# yacc1.net
KiCad netlist of a schematic drawn in EAGLE
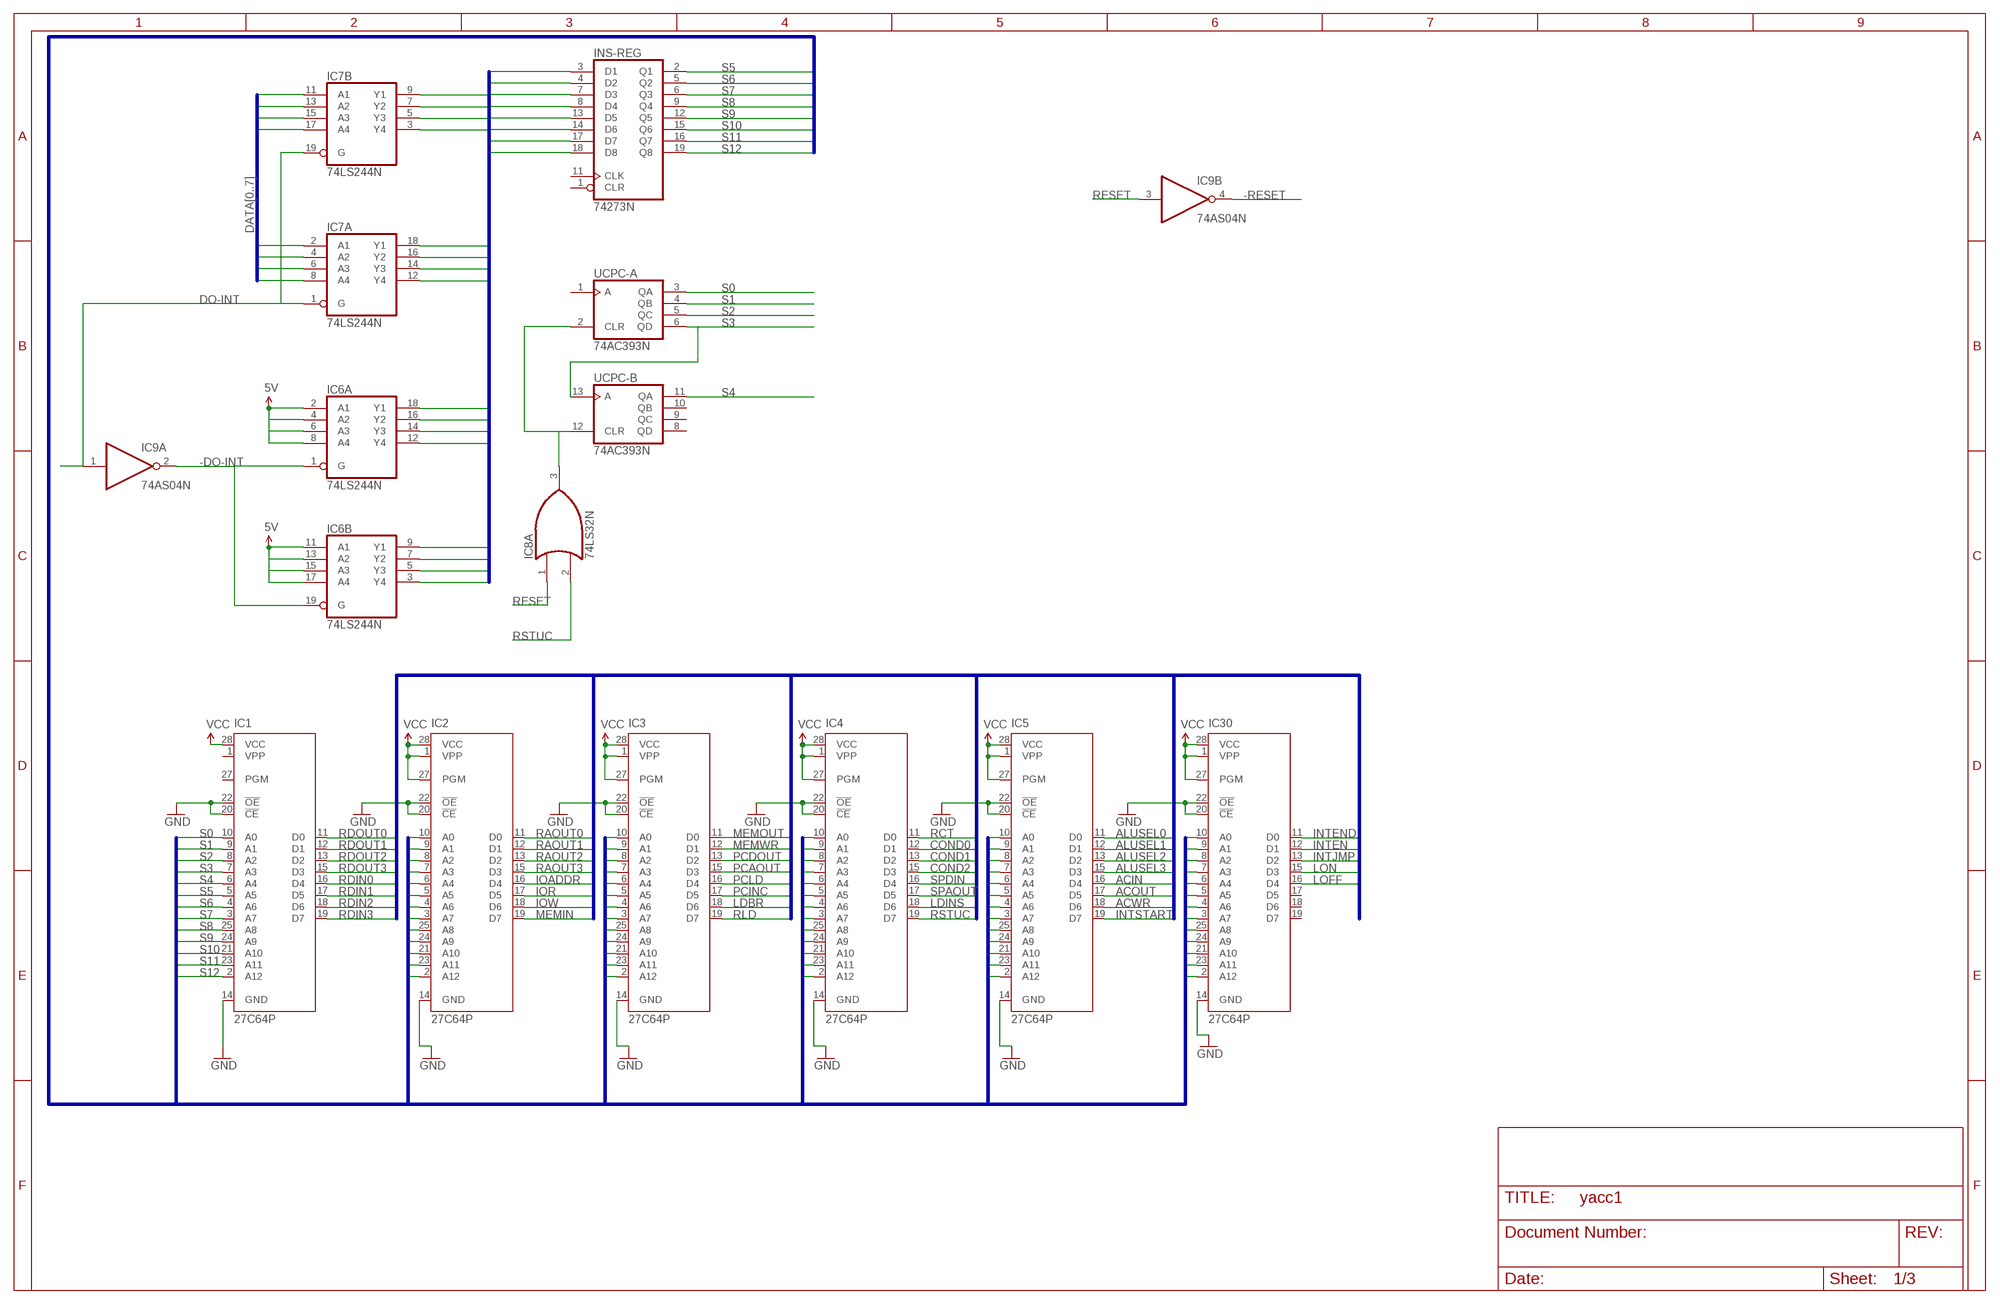
[diagram p0: schematic, sheet 1]
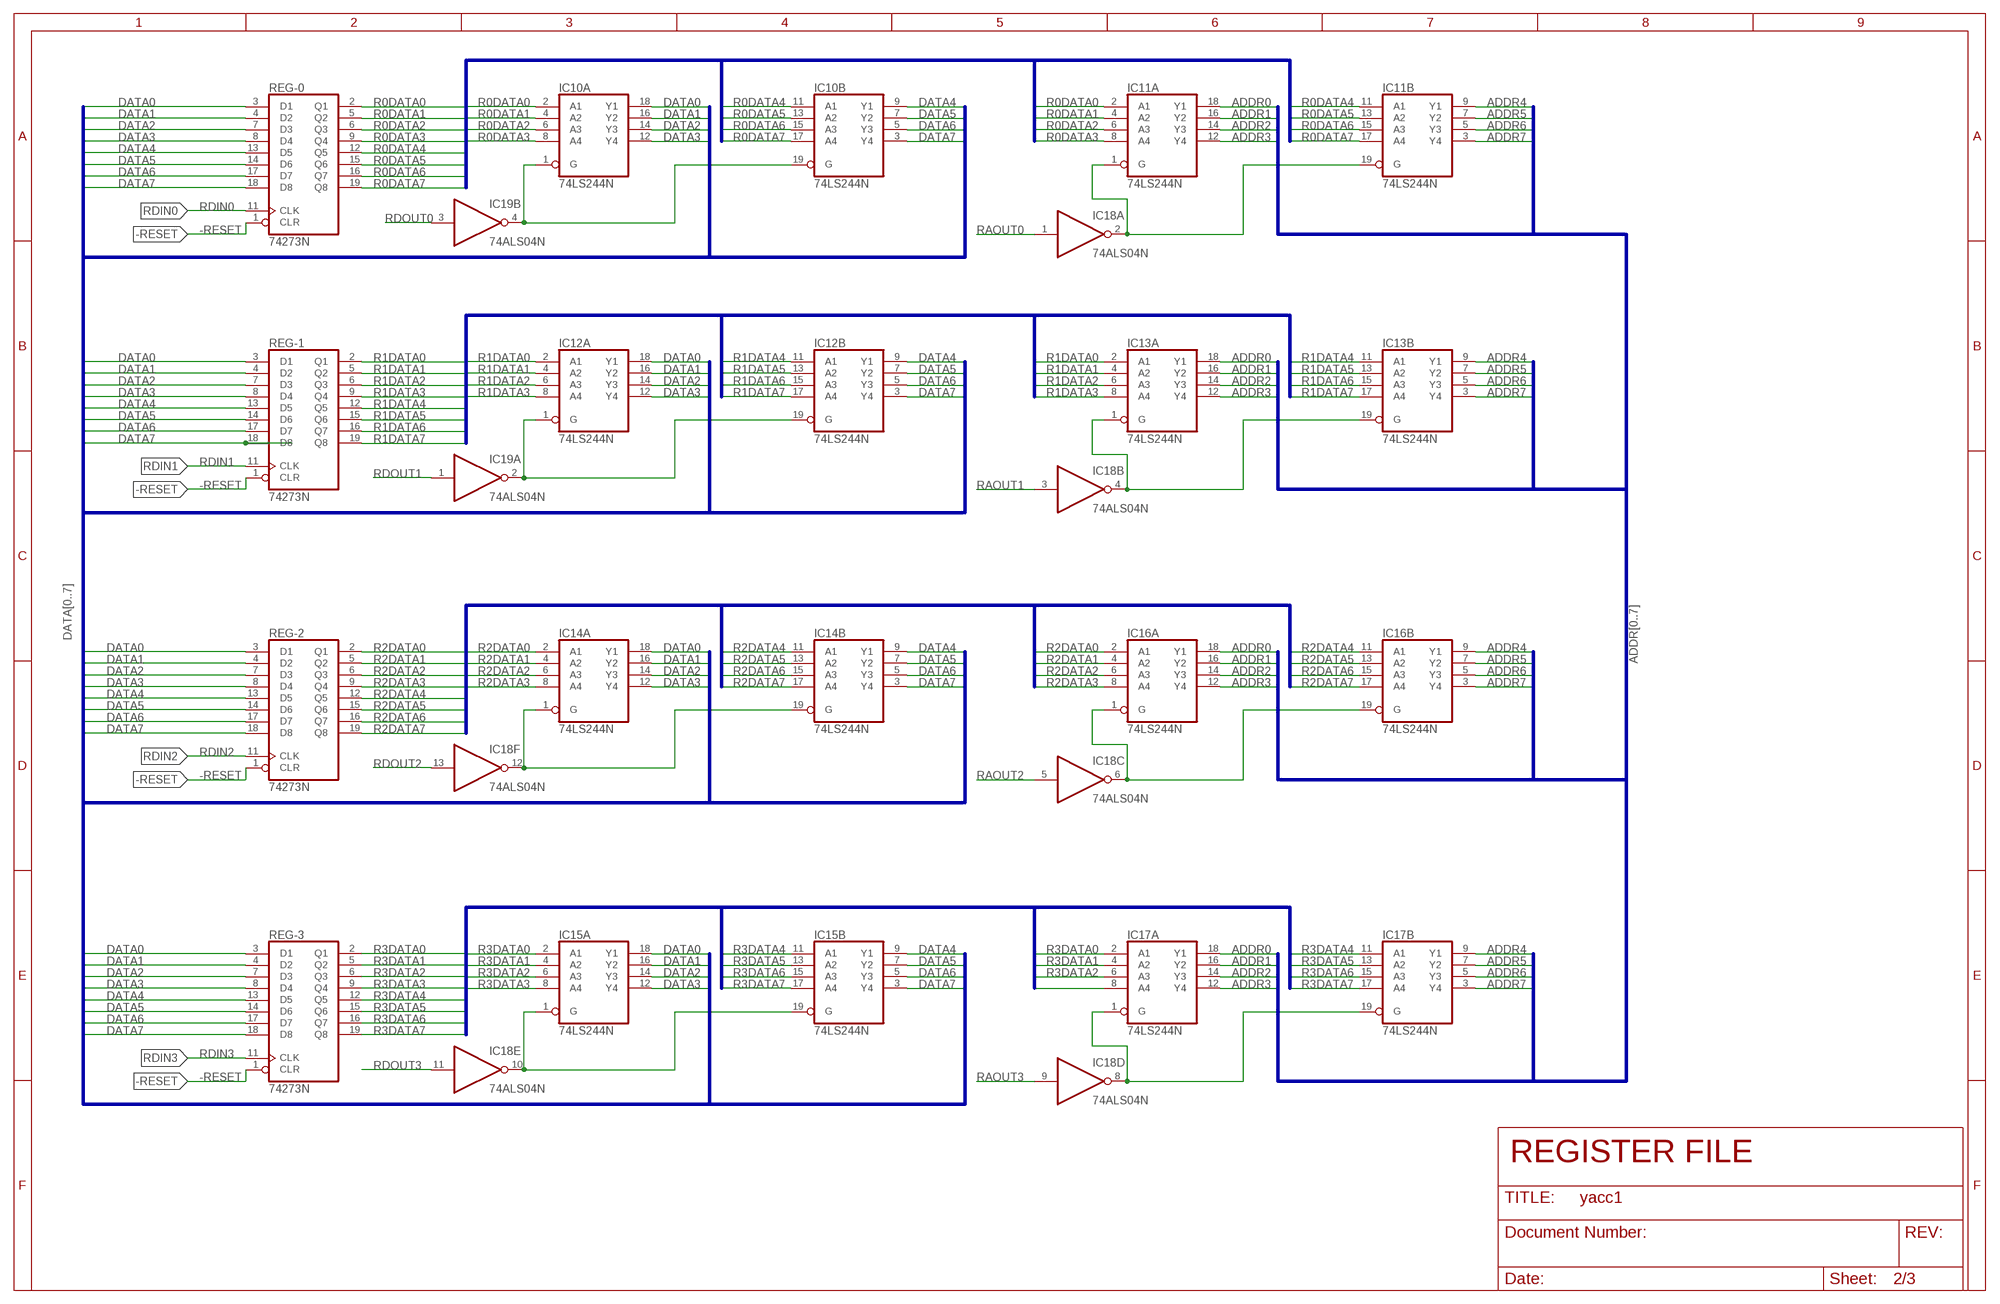
[diagram p1: schematic, sheet 2]
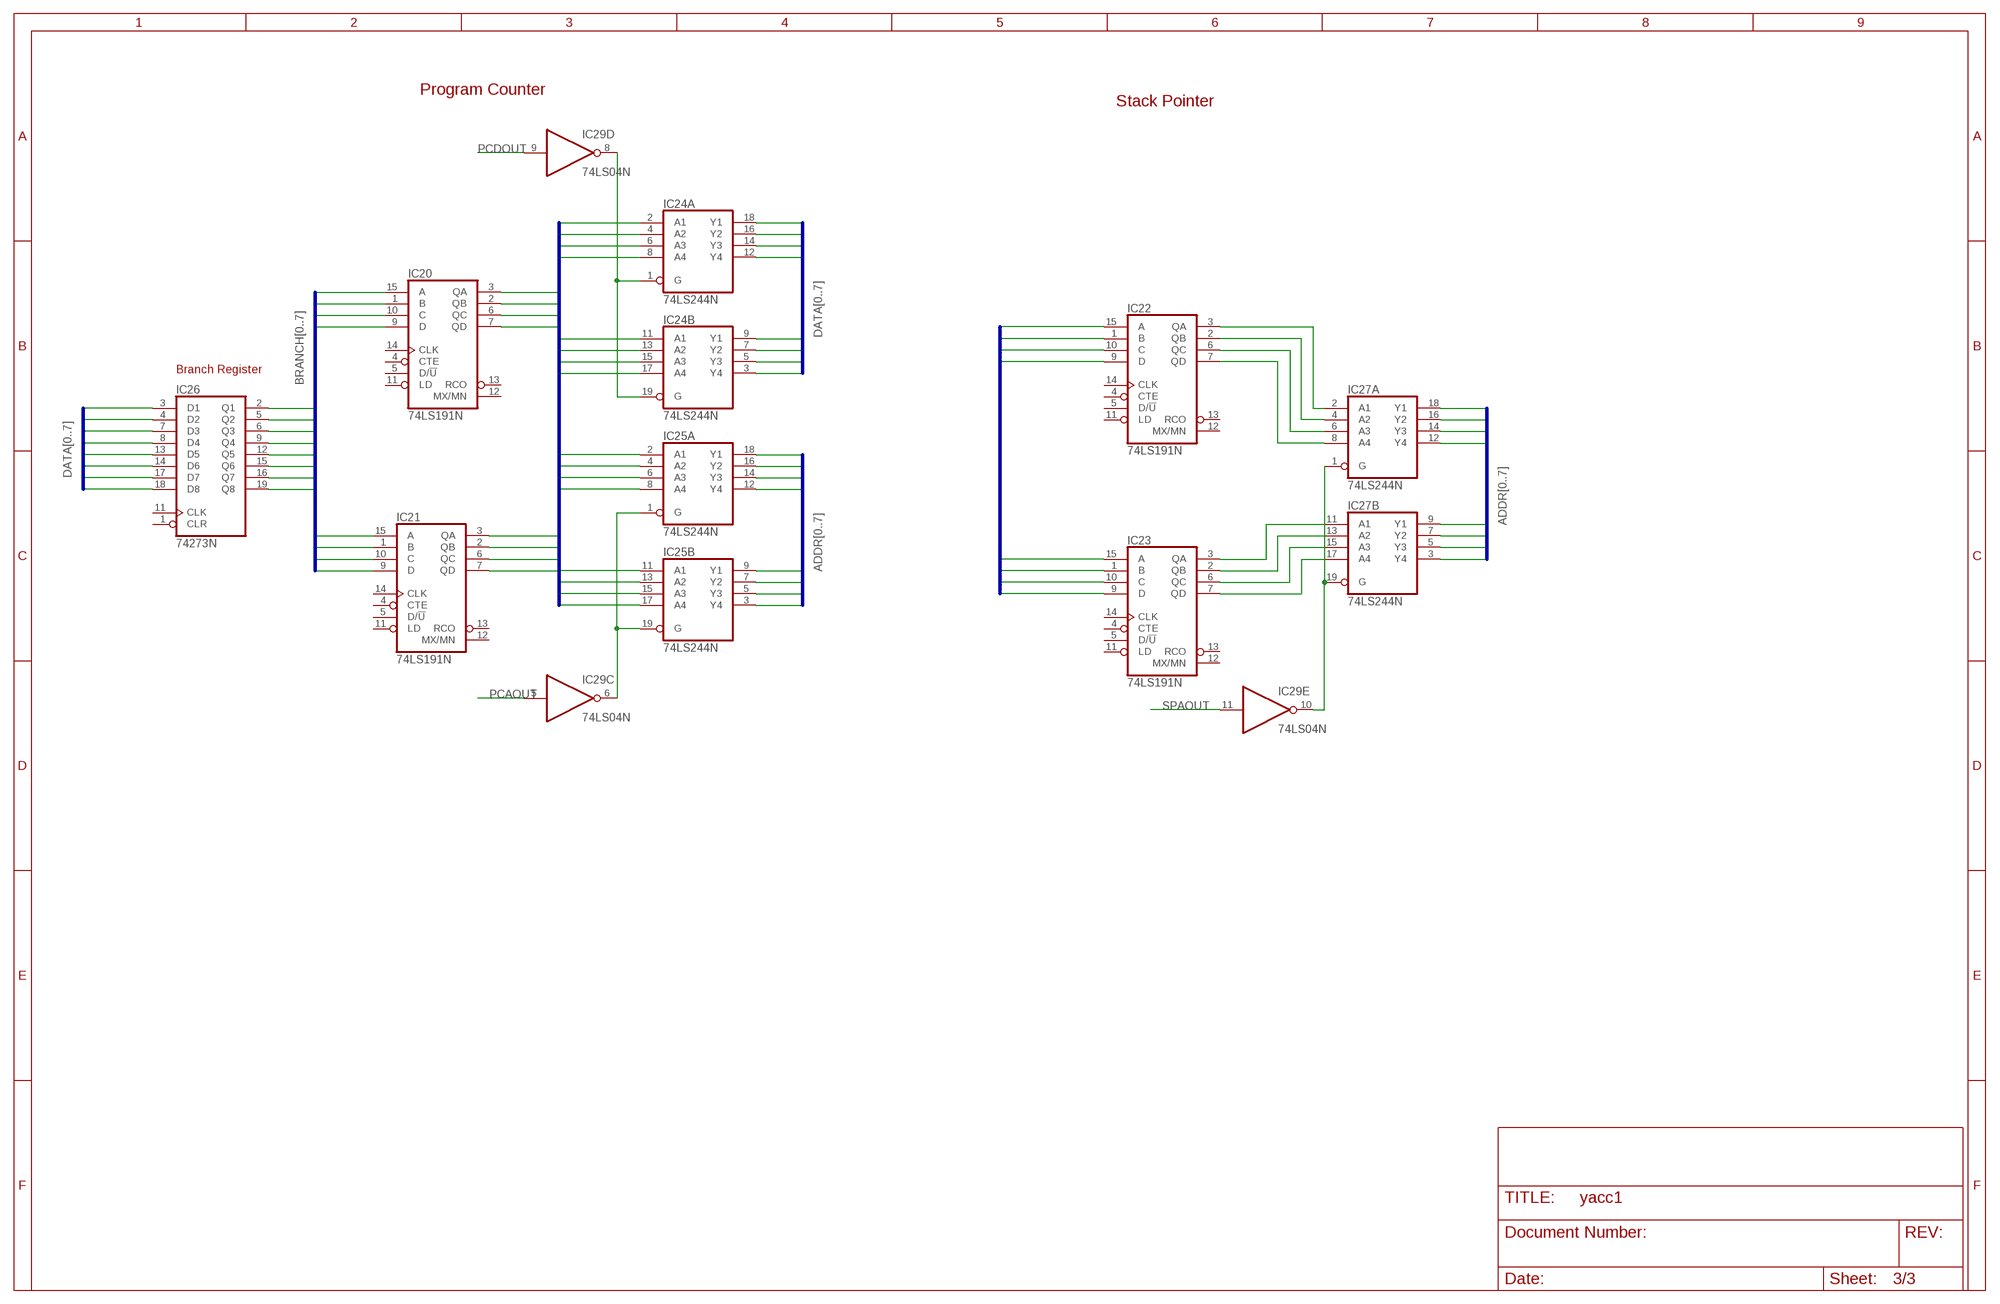
[diagram p2: schematic, sheet 3]

(export (version "E")
  (design (tool "Eeschema 10.0.6"))
  (components
    (comp (ref "IC20")
      (value "74LS191N")
      (footprint "eagle-import:DIL16")
      (libsource (lib "eagle-import") (part "74191NLS"))
    )
    (comp (ref "IC21")
      (value "74LS191N")
      (footprint "eagle-import:DIL16")
      (libsource (lib "eagle-import") (part "74191NLS"))
    )
    (comp (ref "IC22")
      (value "74LS191N")
      (footprint "eagle-import:DIL16")
      (libsource (lib "eagle-import") (part "74191NLS"))
    )
    (comp (ref "IC23")
      (value "74LS191N")
      (footprint "eagle-import:DIL16")
      (libsource (lib "eagle-import") (part "74191NLS"))
    )
    (comp (ref "IC24")
      (value "74LS244N")
      (footprint "eagle-import:DIL20")
      (libsource (lib "eagle-import") (part "74244NLS"))
    )
    (comp (ref "IC25")
      (value "74LS244N")
      (footprint "eagle-import:DIL20")
      (libsource (lib "eagle-import") (part "74244NLS"))
    )
    (comp (ref "IC26")
      (value "74273N")
      (footprint "eagle-import:DIL20")
      (libsource (lib "eagle-import") (part "74273N"))
    )
    (comp (ref "IC27")
      (value "74LS244N")
      (footprint "eagle-import:DIL20")
      (libsource (lib "eagle-import") (part "74244NLS"))
    )
    (comp (ref "IC29")
      (value "74LS04N")
      (footprint "eagle-import:DIL14")
      (libsource (lib "eagle-import") (part "7404NLS"))
    )
    (comp (ref "IC10")
      (value "74LS244N")
      (footprint "eagle-import:DIL20")
      (libsource (lib "eagle-import") (part "74244NLS"))
    )
    (comp (ref "IC11")
      (value "74LS244N")
      (footprint "eagle-import:DIL20")
      (libsource (lib "eagle-import") (part "74244NLS"))
    )
    (comp (ref "IC12")
      (value "74LS244N")
      (footprint "eagle-import:DIL20")
      (libsource (lib "eagle-import") (part "74244NLS"))
    )
    (comp (ref "IC13")
      (value "74LS244N")
      (footprint "eagle-import:DIL20")
      (libsource (lib "eagle-import") (part "74244NLS"))
    )
    (comp (ref "IC14")
      (value "74LS244N")
      (footprint "eagle-import:DIL20")
      (libsource (lib "eagle-import") (part "74244NLS"))
    )
    (comp (ref "IC15")
      (value "74LS244N")
      (footprint "eagle-import:DIL20")
      (libsource (lib "eagle-import") (part "74244NLS"))
    )
    (comp (ref "IC16")
      (value "74LS244N")
      (footprint "eagle-import:DIL20")
      (libsource (lib "eagle-import") (part "74244NLS"))
    )
    (comp (ref "IC17")
      (value "74LS244N")
      (footprint "eagle-import:DIL20")
      (libsource (lib "eagle-import") (part "74244NLS"))
    )
    (comp (ref "IC18")
      (value "74ALS04N")
      (footprint "eagle-import:DIL14")
      (libsource (lib "eagle-import") (part "7404NALS"))
    )
    (comp (ref "IC19")
      (value "74ALS04N")
      (footprint "eagle-import:DIL14")
      (libsource (lib "eagle-import") (part "7404NALS"))
    )
    (comp (ref "REG-0")
      (value "74273N")
      (footprint "eagle-import:DIL20")
      (libsource (lib "eagle-import") (part "74273N"))
    )
    (comp (ref "REG-1")
      (value "74273N")
      (footprint "eagle-import:DIL20")
      (libsource (lib "eagle-import") (part "74273N"))
    )
    (comp (ref "REG-2")
      (value "74273N")
      (footprint "eagle-import:DIL20")
      (libsource (lib "eagle-import") (part "74273N"))
    )
    (comp (ref "REG-3")
      (value "74273N")
      (footprint "eagle-import:DIL20")
      (libsource (lib "eagle-import") (part "74273N"))
    )
    (comp (ref "IC1")
      (value "27C64P")
      (footprint "eagle-import:DIL28-6")
      (fields (field (name "MF") "Arrow Electronics") (field (name "MPN") "M27C64A-10F1"))
      (libsource (lib "eagle-import") (part "2764PC"))
    )
    (comp (ref "IC2")
      (value "27C64P")
      (footprint "eagle-import:DIL28-6")
      (fields (field (name "MF") "Arrow Electronics") (field (name "MPN") "M27C64A-10F1"))
      (libsource (lib "eagle-import") (part "2764PC"))
    )
    (comp (ref "IC3")
      (value "27C64P")
      (footprint "eagle-import:DIL28-6")
      (fields (field (name "MF") "Arrow Electronics") (field (name "MPN") "M27C64A-10F1"))
      (libsource (lib "eagle-import") (part "2764PC"))
    )
    (comp (ref "IC4")
      (value "27C64P")
      (footprint "eagle-import:DIL28-6")
      (fields (field (name "MF") "Arrow Electronics") (field (name "MPN") "M27C64A-10F1"))
      (libsource (lib "eagle-import") (part "2764PC"))
    )
    (comp (ref "IC5")
      (value "27C64P")
      (footprint "eagle-import:DIL28-6")
      (fields (field (name "MF") "Arrow Electronics") (field (name "MPN") "M27C64A-10F1"))
      (libsource (lib "eagle-import") (part "2764PC"))
    )
    (comp (ref "IC6")
      (value "74LS244N")
      (footprint "eagle-import:DIL20")
      (libsource (lib "eagle-import") (part "74244NLS"))
    )
    (comp (ref "IC7")
      (value "74LS244N")
      (footprint "eagle-import:DIL20")
      (libsource (lib "eagle-import") (part "74244NLS"))
    )
    (comp (ref "IC8")
      (value "74LS32N")
      (footprint "eagle-import:DIL14")
      (libsource (lib "eagle-import") (part "7432NLS"))
    )
    (comp (ref "IC9")
      (value "74AS04N")
      (footprint "eagle-import:DIL14")
      (libsource (lib "eagle-import") (part "7404NAS"))
    )
    (comp (ref "IC30")
      (value "27C64P")
      (footprint "eagle-import:DIL28-6")
      (fields (field (name "MF") "Arrow Electronics") (field (name "MPN") "M27C64A-10F1"))
      (libsource (lib "eagle-import") (part "2764PC"))
    )
    (comp (ref "INS-REG")
      (value "74273N")
      (footprint "eagle-import:DIL20")
      (libsource (lib "eagle-import") (part "74273N"))
    )
    (comp (ref "UCPC-")
      (value "74AC393N")
      (footprint "eagle-import:DIL14")
      (libsource (lib "eagle-import") (part "74393NAC"))
    )
  )
  (nets
    (net (code "2") (name "-DO-INT") (class "Default")
      (node (ref "IC6") (pin "1") (pinfunction "G_1") (pintype "input"))
      (node (ref "IC6") (pin "19") (pinfunction "G_19") (pintype "input"))
      (node (ref "IC9") (pin "2") (pinfunction "O_2") (pintype "output"))
    )
    (net (code "3") (name "-RESET") (class "Default")
      (node (ref "IC9") (pin "4") (pinfunction "O_4") (pintype "output"))
      (node (ref "REG-0") (pin "1") (pinfunction "CLR_1") (pintype "input"))
      (node (ref "REG-1") (pin "1") (pinfunction "CLR_1") (pintype "input"))
      (node (ref "REG-2") (pin "1") (pinfunction "CLR_1") (pintype "input"))
      (node (ref "REG-3") (pin "1") (pinfunction "CLR_1") (pintype "input"))
    )
    (net (code "10") (name "5V") (class "Default")
      (node (ref "IC6") (pin "11") (pinfunction "A1_11") (pintype "input"))
      (node (ref "IC6") (pin "13") (pinfunction "A2_13") (pintype "input"))
      (node (ref "IC6") (pin "15") (pinfunction "A3_15") (pintype "input"))
      (node (ref "IC6") (pin "17") (pinfunction "A4_17") (pintype "input"))
      (node (ref "IC6") (pin "2") (pinfunction "A1_2") (pintype "input"))
      (node (ref "IC6") (pin "4") (pinfunction "A2_4") (pintype "input"))
      (node (ref "IC6") (pin "6") (pinfunction "A3_6") (pintype "input"))
      (node (ref "IC6") (pin "8") (pinfunction "A4_8") (pintype "input"))
    )
    (net (code "11") (name "ACIN") (class "Default")
      (node (ref "IC5") (pin "16") (pinfunction "D4_16") (pintype "tri_state"))
    )
    (net (code "12") (name "ACOUT") (class "Default")
      (node (ref "IC5") (pin "17") (pinfunction "D5_17") (pintype "tri_state"))
    )
    (net (code "13") (name "ACWR") (class "Default")
      (node (ref "IC5") (pin "18") (pinfunction "D6_18") (pintype "tri_state"))
    )
    (net (code "14") (name "ADDR0") (class "Default")
      (node (ref "IC11") (pin "18") (pinfunction "Y1_18") (pintype "tri_state"))
      (node (ref "IC13") (pin "18") (pinfunction "Y1_18") (pintype "tri_state"))
      (node (ref "IC16") (pin "18") (pinfunction "Y1_18") (pintype "tri_state"))
      (node (ref "IC17") (pin "18") (pinfunction "Y1_18") (pintype "tri_state"))
      (node (ref "IC25") (pin "18") (pinfunction "Y1_18") (pintype "tri_state"))
    )
    (net (code "15") (name "ADDR1") (class "Default")
      (node (ref "IC11") (pin "16") (pinfunction "Y2_16") (pintype "tri_state"))
      (node (ref "IC13") (pin "16") (pinfunction "Y2_16") (pintype "tri_state"))
      (node (ref "IC16") (pin "16") (pinfunction "Y2_16") (pintype "tri_state"))
      (node (ref "IC17") (pin "16") (pinfunction "Y2_16") (pintype "tri_state"))
    )
    (net (code "16") (name "ADDR2") (class "Default")
      (node (ref "IC11") (pin "14") (pinfunction "Y3_14") (pintype "tri_state"))
      (node (ref "IC13") (pin "14") (pinfunction "Y3_14") (pintype "tri_state"))
      (node (ref "IC16") (pin "14") (pinfunction "Y3_14") (pintype "tri_state"))
      (node (ref "IC17") (pin "14") (pinfunction "Y3_14") (pintype "tri_state"))
      (node (ref "IC25") (pin "14") (pinfunction "Y3_14") (pintype "tri_state"))
      (node (ref "IC25") (pin "16") (pinfunction "Y2_16") (pintype "tri_state"))
    )
    (net (code "17") (name "ADDR3") (class "Default")
      (node (ref "IC11") (pin "12") (pinfunction "Y4_12") (pintype "tri_state"))
      (node (ref "IC13") (pin "12") (pinfunction "Y4_12") (pintype "tri_state"))
      (node (ref "IC16") (pin "12") (pinfunction "Y4_12") (pintype "tri_state"))
      (node (ref "IC17") (pin "12") (pinfunction "Y4_12") (pintype "tri_state"))
      (node (ref "IC25") (pin "12") (pinfunction "Y4_12") (pintype "tri_state"))
    )
    (net (code "18") (name "ADDR4") (class "Default")
      (node (ref "IC11") (pin "9") (pinfunction "Y1_9") (pintype "tri_state"))
      (node (ref "IC13") (pin "9") (pinfunction "Y1_9") (pintype "tri_state"))
      (node (ref "IC16") (pin "9") (pinfunction "Y1_9") (pintype "tri_state"))
      (node (ref "IC17") (pin "9") (pinfunction "Y1_9") (pintype "tri_state"))
      (node (ref "IC25") (pin "9") (pinfunction "Y1_9") (pintype "tri_state"))
    )
    (net (code "19") (name "ADDR5") (class "Default")
      (node (ref "IC11") (pin "7") (pinfunction "Y2_7") (pintype "tri_state"))
      (node (ref "IC13") (pin "7") (pinfunction "Y2_7") (pintype "tri_state"))
      (node (ref "IC16") (pin "7") (pinfunction "Y2_7") (pintype "tri_state"))
      (node (ref "IC17") (pin "7") (pinfunction "Y2_7") (pintype "tri_state"))
      (node (ref "IC25") (pin "7") (pinfunction "Y2_7") (pintype "tri_state"))
    )
    (net (code "20") (name "ADDR6") (class "Default")
      (node (ref "IC11") (pin "5") (pinfunction "Y3_5") (pintype "tri_state"))
      (node (ref "IC13") (pin "5") (pinfunction "Y3_5") (pintype "tri_state"))
      (node (ref "IC16") (pin "5") (pinfunction "Y3_5") (pintype "tri_state"))
      (node (ref "IC17") (pin "5") (pinfunction "Y3_5") (pintype "tri_state"))
      (node (ref "IC25") (pin "5") (pinfunction "Y3_5") (pintype "tri_state"))
    )
    (net (code "21") (name "ADDR7") (class "Default")
      (node (ref "IC11") (pin "3") (pinfunction "Y4_3") (pintype "tri_state"))
      (node (ref "IC13") (pin "3") (pinfunction "Y4_3") (pintype "tri_state"))
      (node (ref "IC16") (pin "3") (pinfunction "Y4_3") (pintype "tri_state"))
      (node (ref "IC17") (pin "3") (pinfunction "Y4_3") (pintype "tri_state"))
      (node (ref "IC25") (pin "3") (pinfunction "Y4_3") (pintype "tri_state"))
    )
    (net (code "22") (name "ADDR9") (class "Default")
      (node (ref "IC27") (pin "14") (pinfunction "Y3_14") (pintype "tri_state"))
      (node (ref "IC27") (pin "16") (pinfunction "Y2_16") (pintype "tri_state"))
    )
    (net (code "23") (name "ALUSEL0") (class "Default")
      (node (ref "IC5") (pin "11") (pinfunction "D0_11") (pintype "tri_state"))
    )
    (net (code "24") (name "ALUSEL1") (class "Default")
      (node (ref "IC5") (pin "12") (pinfunction "D1_12") (pintype "tri_state"))
    )
    (net (code "25") (name "ALUSEL2") (class "Default")
      (node (ref "IC5") (pin "13") (pinfunction "D2_13") (pintype "tri_state"))
    )
    (net (code "26") (name "ALUSEL3") (class "Default")
      (node (ref "IC5") (pin "15") (pinfunction "D3_15") (pintype "tri_state"))
    )
    (net (code "27") (name "BRANCH0") (class "Default")
      (node (ref "IC20") (pin "15") (pinfunction "A_15") (pintype "input"))
      (node (ref "IC26") (pin "2") (pinfunction "Q1_2") (pintype "output"))
    )
    (net (code "28") (name "BRANCH1") (class "Default")
      (node (ref "IC20") (pin "1") (pinfunction "B_1") (pintype "input"))
      (node (ref "IC26") (pin "5") (pinfunction "Q2_5") (pintype "output"))
    )
    (net (code "29") (name "BRANCH2") (class "Default")
      (node (ref "IC20") (pin "10") (pinfunction "C_10") (pintype "input"))
      (node (ref "IC26") (pin "6") (pinfunction "Q3_6") (pintype "output"))
    )
    (net (code "30") (name "BRANCH3") (class "Default")
      (node (ref "IC20") (pin "9") (pinfunction "D_9") (pintype "input"))
      (node (ref "IC26") (pin "9") (pinfunction "Q4_9") (pintype "output"))
    )
    (net (code "31") (name "BRANCH4") (class "Default")
      (node (ref "IC21") (pin "15") (pinfunction "A_15") (pintype "input"))
      (node (ref "IC26") (pin "12") (pinfunction "Q5_12") (pintype "output"))
    )
    (net (code "32") (name "BRANCH5") (class "Default")
      (node (ref "IC21") (pin "1") (pinfunction "B_1") (pintype "input"))
      (node (ref "IC26") (pin "15") (pinfunction "Q6_15") (pintype "output"))
    )
    (net (code "33") (name "BRANCH6") (class "Default")
      (node (ref "IC21") (pin "10") (pinfunction "C_10") (pintype "input"))
      (node (ref "IC26") (pin "16") (pinfunction "Q7_16") (pintype "output"))
    )
    (net (code "34") (name "BRANCH7") (class "Default")
      (node (ref "IC21") (pin "9") (pinfunction "D_9") (pintype "input"))
      (node (ref "IC26") (pin "19") (pinfunction "Q8_19") (pintype "output"))
    )
    (net (code "35") (name "COND0") (class "Default")
      (node (ref "IC4") (pin "12") (pinfunction "D1_12") (pintype "tri_state"))
    )
    (net (code "36") (name "COND1") (class "Default")
      (node (ref "IC4") (pin "13") (pinfunction "D2_13") (pintype "tri_state"))
    )
    (net (code "37") (name "COND2") (class "Default")
      (node (ref "IC4") (pin "15") (pinfunction "D3_15") (pintype "tri_state"))
    )
    (net (code "38") (name "DATA0") (class "Default")
      (node (ref "IC10") (pin "18") (pinfunction "Y1_18") (pintype "tri_state"))
      (node (ref "IC12") (pin "18") (pinfunction "Y1_18") (pintype "tri_state"))
      (node (ref "IC14") (pin "18") (pinfunction "Y1_18") (pintype "tri_state"))
      (node (ref "IC15") (pin "18") (pinfunction "Y1_18") (pintype "tri_state"))
      (node (ref "IC22") (pin "15") (pinfunction "A_15") (pintype "input"))
      (node (ref "IC24") (pin "18") (pinfunction "Y1_18") (pintype "tri_state"))
      (node (ref "IC26") (pin "3") (pinfunction "D1_3") (pintype "input"))
      (node (ref "IC7") (pin "11") (pinfunction "A1_11") (pintype "input"))
      (node (ref "REG-0") (pin "3") (pinfunction "D1_3") (pintype "input"))
      (node (ref "REG-1") (pin "3") (pinfunction "D1_3") (pintype "input"))
      (node (ref "REG-2") (pin "3") (pinfunction "D1_3") (pintype "input"))
      (node (ref "REG-3") (pin "3") (pinfunction "D1_3") (pintype "input"))
    )
    (net (code "39") (name "DATA1") (class "Default")
      (node (ref "IC10") (pin "16") (pinfunction "Y2_16") (pintype "tri_state"))
      (node (ref "IC12") (pin "16") (pinfunction "Y2_16") (pintype "tri_state"))
      (node (ref "IC14") (pin "16") (pinfunction "Y2_16") (pintype "tri_state"))
      (node (ref "IC15") (pin "16") (pinfunction "Y2_16") (pintype "tri_state"))
      (node (ref "IC22") (pin "1") (pinfunction "B_1") (pintype "input"))
      (node (ref "IC24") (pin "16") (pinfunction "Y2_16") (pintype "tri_state"))
      (node (ref "IC26") (pin "4") (pinfunction "D2_4") (pintype "input"))
      (node (ref "IC7") (pin "13") (pinfunction "A2_13") (pintype "input"))
      (node (ref "REG-0") (pin "4") (pinfunction "D2_4") (pintype "input"))
      (node (ref "REG-1") (pin "4") (pinfunction "D2_4") (pintype "input"))
      (node (ref "REG-2") (pin "4") (pinfunction "D2_4") (pintype "input"))
      (node (ref "REG-3") (pin "4") (pinfunction "D2_4") (pintype "input"))
    )
    (net (code "40") (name "DATA2") (class "Default")
      (node (ref "IC10") (pin "14") (pinfunction "Y3_14") (pintype "tri_state"))
      (node (ref "IC12") (pin "14") (pinfunction "Y3_14") (pintype "tri_state"))
      (node (ref "IC14") (pin "14") (pinfunction "Y3_14") (pintype "tri_state"))
      (node (ref "IC15") (pin "14") (pinfunction "Y3_14") (pintype "tri_state"))
      (node (ref "IC22") (pin "10") (pinfunction "C_10") (pintype "input"))
      (node (ref "IC24") (pin "14") (pinfunction "Y3_14") (pintype "tri_state"))
      (node (ref "IC26") (pin "7") (pinfunction "D3_7") (pintype "input"))
      (node (ref "IC7") (pin "15") (pinfunction "A3_15") (pintype "input"))
      (node (ref "REG-0") (pin "7") (pinfunction "D3_7") (pintype "input"))
      (node (ref "REG-1") (pin "7") (pinfunction "D3_7") (pintype "input"))
      (node (ref "REG-2") (pin "7") (pinfunction "D3_7") (pintype "input"))
      (node (ref "REG-3") (pin "7") (pinfunction "D3_7") (pintype "input"))
    )
    (net (code "41") (name "DATA3") (class "Default")
      (node (ref "IC10") (pin "12") (pinfunction "Y4_12") (pintype "tri_state"))
      (node (ref "IC12") (pin "12") (pinfunction "Y4_12") (pintype "tri_state"))
      (node (ref "IC14") (pin "12") (pinfunction "Y4_12") (pintype "tri_state"))
      (node (ref "IC15") (pin "12") (pinfunction "Y4_12") (pintype "tri_state"))
      (node (ref "IC22") (pin "9") (pinfunction "D_9") (pintype "input"))
      (node (ref "IC24") (pin "12") (pinfunction "Y4_12") (pintype "tri_state"))
      (node (ref "IC26") (pin "8") (pinfunction "D4_8") (pintype "input"))
      (node (ref "IC7") (pin "17") (pinfunction "A4_17") (pintype "input"))
      (node (ref "REG-0") (pin "8") (pinfunction "D4_8") (pintype "input"))
      (node (ref "REG-1") (pin "8") (pinfunction "D4_8") (pintype "input"))
      (node (ref "REG-2") (pin "8") (pinfunction "D4_8") (pintype "input"))
      (node (ref "REG-3") (pin "8") (pinfunction "D4_8") (pintype "input"))
    )
    (net (code "42") (name "DATA4") (class "Default")
      (node (ref "IC10") (pin "9") (pinfunction "Y1_9") (pintype "tri_state"))
      (node (ref "IC12") (pin "9") (pinfunction "Y1_9") (pintype "tri_state"))
      (node (ref "IC14") (pin "9") (pinfunction "Y1_9") (pintype "tri_state"))
      (node (ref "IC15") (pin "9") (pinfunction "Y1_9") (pintype "tri_state"))
      (node (ref "IC23") (pin "15") (pinfunction "A_15") (pintype "input"))
      (node (ref "IC24") (pin "9") (pinfunction "Y1_9") (pintype "tri_state"))
      (node (ref "IC26") (pin "13") (pinfunction "D5_13") (pintype "input"))
      (node (ref "IC7") (pin "2") (pinfunction "A1_2") (pintype "input"))
      (node (ref "REG-0") (pin "13") (pinfunction "D5_13") (pintype "input"))
      (node (ref "REG-1") (pin "13") (pinfunction "D5_13") (pintype "input"))
      (node (ref "REG-2") (pin "13") (pinfunction "D5_13") (pintype "input"))
      (node (ref "REG-3") (pin "13") (pinfunction "D5_13") (pintype "input"))
    )
    (net (code "43") (name "DATA5") (class "Default")
      (node (ref "IC10") (pin "7") (pinfunction "Y2_7") (pintype "tri_state"))
      (node (ref "IC12") (pin "7") (pinfunction "Y2_7") (pintype "tri_state"))
      (node (ref "IC14") (pin "7") (pinfunction "Y2_7") (pintype "tri_state"))
      (node (ref "IC15") (pin "7") (pinfunction "Y2_7") (pintype "tri_state"))
      (node (ref "IC23") (pin "1") (pinfunction "B_1") (pintype "input"))
      (node (ref "IC24") (pin "7") (pinfunction "Y2_7") (pintype "tri_state"))
      (node (ref "IC26") (pin "14") (pinfunction "D6_14") (pintype "input"))
      (node (ref "IC7") (pin "4") (pinfunction "A2_4") (pintype "input"))
      (node (ref "REG-0") (pin "14") (pinfunction "D6_14") (pintype "input"))
      (node (ref "REG-1") (pin "14") (pinfunction "D6_14") (pintype "input"))
      (node (ref "REG-2") (pin "14") (pinfunction "D6_14") (pintype "input"))
      (node (ref "REG-3") (pin "14") (pinfunction "D6_14") (pintype "input"))
    )
    (net (code "44") (name "DATA6") (class "Default")
      (node (ref "IC10") (pin "5") (pinfunction "Y3_5") (pintype "tri_state"))
      (node (ref "IC12") (pin "5") (pinfunction "Y3_5") (pintype "tri_state"))
      (node (ref "IC14") (pin "5") (pinfunction "Y3_5") (pintype "tri_state"))
      (node (ref "IC15") (pin "5") (pinfunction "Y3_5") (pintype "tri_state"))
      (node (ref "IC23") (pin "10") (pinfunction "C_10") (pintype "input"))
      (node (ref "IC24") (pin "5") (pinfunction "Y3_5") (pintype "tri_state"))
      (node (ref "IC26") (pin "17") (pinfunction "D7_17") (pintype "input"))
      (node (ref "IC7") (pin "6") (pinfunction "A3_6") (pintype "input"))
      (node (ref "REG-0") (pin "17") (pinfunction "D7_17") (pintype "input"))
      (node (ref "REG-1") (pin "17") (pinfunction "D7_17") (pintype "input"))
      (node (ref "REG-2") (pin "17") (pinfunction "D7_17") (pintype "input"))
      (node (ref "REG-3") (pin "17") (pinfunction "D7_17") (pintype "input"))
    )
    (net (code "45") (name "DATA7") (class "Default")
      (node (ref "IC10") (pin "3") (pinfunction "Y4_3") (pintype "tri_state"))
      (node (ref "IC12") (pin "3") (pinfunction "Y4_3") (pintype "tri_state"))
      (node (ref "IC14") (pin "3") (pinfunction "Y4_3") (pintype "tri_state"))
      (node (ref "IC15") (pin "3") (pinfunction "Y4_3") (pintype "tri_state"))
      (node (ref "IC23") (pin "9") (pinfunction "D_9") (pintype "input"))
      (node (ref "IC24") (pin "3") (pinfunction "Y4_3") (pintype "tri_state"))
      (node (ref "IC26") (pin "18") (pinfunction "D8_18") (pintype "input"))
      (node (ref "IC7") (pin "8") (pinfunction "A4_8") (pintype "input"))
      (node (ref "REG-0") (pin "18") (pinfunction "D8_18") (pintype "input"))
      (node (ref "REG-1") (pin "18") (pinfunction "D8_18") (pintype "input"))
      (node (ref "REG-2") (pin "18") (pinfunction "D8_18") (pintype "input"))
      (node (ref "REG-3") (pin "18") (pinfunction "D8_18") (pintype "input"))
    )
    (net (code "46") (name "DINS0") (class "Default")
      (node (ref "IC6") (pin "18") (pinfunction "Y1_18") (pintype "tri_state"))
      (node (ref "IC7") (pin "9") (pinfunction "Y1_9") (pintype "tri_state"))
      (node (ref "INS-REG") (pin "3") (pinfunction "D1_3") (pintype "input"))
    )
    (net (code "47") (name "DINS1") (class "Default")
      (node (ref "IC6") (pin "16") (pinfunction "Y2_16") (pintype "tri_state"))
      (node (ref "IC7") (pin "7") (pinfunction "Y2_7") (pintype "tri_state"))
      (node (ref "INS-REG") (pin "4") (pinfunction "D2_4") (pintype "input"))
    )
    (net (code "48") (name "DINS2") (class "Default")
      (node (ref "IC6") (pin "14") (pinfunction "Y3_14") (pintype "tri_state"))
      (node (ref "IC7") (pin "5") (pinfunction "Y3_5") (pintype "tri_state"))
      (node (ref "INS-REG") (pin "7") (pinfunction "D3_7") (pintype "input"))
    )
    (net (code "49") (name "DINS3") (class "Default")
      (node (ref "IC6") (pin "12") (pinfunction "Y4_12") (pintype "tri_state"))
      (node (ref "IC7") (pin "3") (pinfunction "Y4_3") (pintype "tri_state"))
      (node (ref "INS-REG") (pin "8") (pinfunction "D4_8") (pintype "input"))
    )
    (net (code "50") (name "DINS4") (class "Default")
      (node (ref "IC6") (pin "9") (pinfunction "Y1_9") (pintype "tri_state"))
      (node (ref "IC7") (pin "18") (pinfunction "Y1_18") (pintype "tri_state"))
      (node (ref "INS-REG") (pin "13") (pinfunction "D5_13") (pintype "input"))
    )
    (net (code "51") (name "DINS5") (class "Default")
      (node (ref "IC6") (pin "7") (pinfunction "Y2_7") (pintype "tri_state"))
      (node (ref "IC7") (pin "16") (pinfunction "Y2_16") (pintype "tri_state"))
      (node (ref "INS-REG") (pin "14") (pinfunction "D6_14") (pintype "input"))
    )
    (net (code "52") (name "DINS6") (class "Default")
      (node (ref "IC6") (pin "5") (pinfunction "Y3_5") (pintype "tri_state"))
      (node (ref "IC7") (pin "14") (pinfunction "Y3_14") (pintype "tri_state"))
      (node (ref "INS-REG") (pin "17") (pinfunction "D7_17") (pintype "input"))
    )
    (net (code "53") (name "DINS7") (class "Default")
      (node (ref "IC6") (pin "3") (pinfunction "Y4_3") (pintype "tri_state"))
      (node (ref "IC7") (pin "12") (pinfunction "Y4_12") (pintype "tri_state"))
      (node (ref "INS-REG") (pin "18") (pinfunction "D8_18") (pintype "input"))
    )
    (net (code "54") (name "DO-INT") (class "Default")
      (node (ref "IC7") (pin "1") (pinfunction "G_1") (pintype "input"))
      (node (ref "IC7") (pin "19") (pinfunction "G_19") (pintype "input"))
      (node (ref "IC9") (pin "1") (pinfunction "I_1") (pintype "input"))
    )
    (net (code "55") (name "GND") (class "Default")
      (node (ref "IC1") (pin "14") (pinfunction "GND_14") (pintype "power_in"))
      (node (ref "IC1") (pin "20") (pinfunction "~{CE}_20") (pintype "input"))
      (node (ref "IC1") (pin "22") (pinfunction "~{OE}_22") (pintype "input"))
      (node (ref "IC2") (pin "14") (pinfunction "GND_14") (pintype "power_in"))
      (node (ref "IC2") (pin "20") (pinfunction "~{CE}_20") (pintype "input"))
      (node (ref "IC2") (pin "22") (pinfunction "~{OE}_22") (pintype "input"))
      (node (ref "IC3") (pin "14") (pinfunction "GND_14") (pintype "power_in"))
      (node (ref "IC3") (pin "20") (pinfunction "~{CE}_20") (pintype "input"))
      (node (ref "IC3") (pin "22") (pinfunction "~{OE}_22") (pintype "input"))
      (node (ref "IC30") (pin "14") (pinfunction "GND_14") (pintype "power_in"))
      (node (ref "IC30") (pin "20") (pinfunction "~{CE}_20") (pintype "input"))
      (node (ref "IC30") (pin "22") (pinfunction "~{OE}_22") (pintype "input"))
      (node (ref "IC4") (pin "14") (pinfunction "GND_14") (pintype "power_in"))
      (node (ref "IC4") (pin "20") (pinfunction "~{CE}_20") (pintype "input"))
      (node (ref "IC4") (pin "22") (pinfunction "~{OE}_22") (pintype "input"))
      (node (ref "IC5") (pin "14") (pinfunction "GND_14") (pintype "power_in"))
      (node (ref "IC5") (pin "20") (pinfunction "~{CE}_20") (pintype "input"))
      (node (ref "IC5") (pin "22") (pinfunction "~{OE}_22") (pintype "input"))
    )
    (net (code "56") (name "INTEN") (class "Default")
      (node (ref "IC30") (pin "12") (pinfunction "D1_12") (pintype "tri_state"))
    )
    (net (code "57") (name "INTEND") (class "Default")
      (node (ref "IC30") (pin "11") (pinfunction "D0_11") (pintype "tri_state"))
    )
    (net (code "58") (name "INTJMP") (class "Default")
      (node (ref "IC30") (pin "13") (pinfunction "D2_13") (pintype "tri_state"))
    )
    (net (code "59") (name "INTSTART") (class "Default")
      (node (ref "IC5") (pin "19") (pinfunction "D7_19") (pintype "tri_state"))
    )
    (net (code "60") (name "IOADDR") (class "Default")
      (node (ref "IC2") (pin "16") (pinfunction "D4_16") (pintype "tri_state"))
    )
    (net (code "61") (name "IOR") (class "Default")
      (node (ref "IC2") (pin "17") (pinfunction "D5_17") (pintype "tri_state"))
    )
    (net (code "62") (name "IOW") (class "Default")
      (node (ref "IC2") (pin "18") (pinfunction "D6_18") (pintype "tri_state"))
    )
    (net (code "63") (name "LDBR") (class "Default")
      (node (ref "IC3") (pin "18") (pinfunction "D6_18") (pintype "tri_state"))
    )
    (net (code "64") (name "LDINS") (class "Default")
      (node (ref "IC4") (pin "18") (pinfunction "D6_18") (pintype "tri_state"))
    )
    (net (code "65") (name "LOFF") (class "Default")
      (node (ref "IC30") (pin "16") (pinfunction "D4_16") (pintype "tri_state"))
    )
    (net (code "66") (name "LON") (class "Default")
      (node (ref "IC30") (pin "15") (pinfunction "D3_15") (pintype "tri_state"))
    )
    (net (code "67") (name "MEMIN") (class "Default")
      (node (ref "IC2") (pin "19") (pinfunction "D7_19") (pintype "tri_state"))
    )
    (net (code "68") (name "MEMOUT") (class "Default")
      (node (ref "IC3") (pin "11") (pinfunction "D0_11") (pintype "tri_state"))
    )
    (net (code "69") (name "MEMWR") (class "Default")
      (node (ref "IC3") (pin "12") (pinfunction "D1_12") (pintype "tri_state"))
    )
    (net (code "70") (name "Net-(IC8A-O)") (class "Default")
      (node (ref "IC8") (pin "3") (pinfunction "O_3") (pintype "output"))
      (node (ref "UCPC-") (pin "12") (pinfunction "CLR_12") (pintype "input"))
      (node (ref "UCPC-") (pin "2") (pinfunction "CLR_2") (pintype "input"))
    )
    (net (code "71") (name "Net-(IC10A-G)") (class "Default")
      (node (ref "IC10") (pin "1") (pinfunction "G_1") (pintype "input"))
      (node (ref "IC10") (pin "19") (pinfunction "G_19") (pintype "input"))
      (node (ref "IC19") (pin "4") (pinfunction "O_4") (pintype "output"))
    )
    (net (code "72") (name "Net-(IC11A-G)") (class "Default")
      (node (ref "IC11") (pin "1") (pinfunction "G_1") (pintype "input"))
      (node (ref "IC11") (pin "19") (pinfunction "G_19") (pintype "input"))
      (node (ref "IC18") (pin "2") (pinfunction "O_2") (pintype "output"))
    )
    (net (code "73") (name "Net-(IC12A-G)") (class "Default")
      (node (ref "IC12") (pin "1") (pinfunction "G_1") (pintype "input"))
      (node (ref "IC12") (pin "19") (pinfunction "G_19") (pintype "input"))
      (node (ref "IC19") (pin "2") (pinfunction "O_2") (pintype "output"))
    )
    (net (code "74") (name "Net-(IC13A-G)") (class "Default")
      (node (ref "IC13") (pin "1") (pinfunction "G_1") (pintype "input"))
      (node (ref "IC13") (pin "19") (pinfunction "G_19") (pintype "input"))
      (node (ref "IC18") (pin "4") (pinfunction "O_4") (pintype "output"))
    )
    (net (code "75") (name "Net-(IC14A-G)") (class "Default")
      (node (ref "IC14") (pin "1") (pinfunction "G_1") (pintype "input"))
      (node (ref "IC14") (pin "19") (pinfunction "G_19") (pintype "input"))
      (node (ref "IC18") (pin "12") (pinfunction "O_12") (pintype "output"))
    )
    (net (code "76") (name "Net-(IC15A-G)") (class "Default")
      (node (ref "IC15") (pin "1") (pinfunction "G_1") (pintype "input"))
      (node (ref "IC15") (pin "19") (pinfunction "G_19") (pintype "input"))
      (node (ref "IC18") (pin "10") (pinfunction "O_10") (pintype "output"))
    )
    (net (code "77") (name "Net-(IC16A-G)") (class "Default")
      (node (ref "IC16") (pin "1") (pinfunction "G_1") (pintype "input"))
      (node (ref "IC16") (pin "19") (pinfunction "G_19") (pintype "input"))
      (node (ref "IC18") (pin "6") (pinfunction "O_6") (pintype "output"))
    )
    (net (code "78") (name "Net-(IC17A-G)") (class "Default")
      (node (ref "IC17") (pin "1") (pinfunction "G_1") (pintype "input"))
      (node (ref "IC17") (pin "19") (pinfunction "G_19") (pintype "input"))
      (node (ref "IC18") (pin "8") (pinfunction "O_8") (pintype "output"))
    )
    (net (code "79") (name "Net-(IC22A-QA)") (class "Default")
      (node (ref "IC22") (pin "3") (pinfunction "QA_3") (pintype "output"))
      (node (ref "IC27") (pin "2") (pinfunction "A1_2") (pintype "input"))
    )
    (net (code "80") (name "Net-(IC22A-QB)") (class "Default")
      (node (ref "IC22") (pin "2") (pinfunction "QB_2") (pintype "output"))
      (node (ref "IC27") (pin "4") (pinfunction "A2_4") (pintype "input"))
    )
    (net (code "81") (name "Net-(IC22A-QC)") (class "Default")
      (node (ref "IC22") (pin "6") (pinfunction "QC_6") (pintype "output"))
      (node (ref "IC27") (pin "6") (pinfunction "A3_6") (pintype "input"))
    )
    (net (code "82") (name "Net-(IC22A-QD)") (class "Default")
      (node (ref "IC22") (pin "7") (pinfunction "QD_7") (pintype "output"))
      (node (ref "IC27") (pin "8") (pinfunction "A4_8") (pintype "input"))
    )
    (net (code "83") (name "Net-(IC23A-QA)") (class "Default")
      (node (ref "IC23") (pin "3") (pinfunction "QA_3") (pintype "output"))
      (node (ref "IC27") (pin "11") (pinfunction "A1_11") (pintype "input"))
    )
    (net (code "84") (name "Net-(IC23A-QB)") (class "Default")
      (node (ref "IC23") (pin "2") (pinfunction "QB_2") (pintype "output"))
      (node (ref "IC27") (pin "13") (pinfunction "A2_13") (pintype "input"))
    )
    (net (code "85") (name "Net-(IC23A-QC)") (class "Default")
      (node (ref "IC23") (pin "6") (pinfunction "QC_6") (pintype "output"))
      (node (ref "IC27") (pin "15") (pinfunction "A3_15") (pintype "input"))
    )
    (net (code "86") (name "Net-(IC23A-QD)") (class "Default")
      (node (ref "IC23") (pin "7") (pinfunction "QD_7") (pintype "output"))
      (node (ref "IC27") (pin "17") (pinfunction "A4_17") (pintype "input"))
    )
    (net (code "87") (name "Net-(IC24A-G)") (class "Default")
      (node (ref "IC24") (pin "1") (pinfunction "G_1") (pintype "input"))
      (node (ref "IC24") (pin "19") (pinfunction "G_19") (pintype "input"))
      (node (ref "IC29") (pin "8") (pinfunction "O_8") (pintype "output"))
    )
    (net (code "88") (name "Net-(IC25A-G)") (class "Default")
      (node (ref "IC25") (pin "1") (pinfunction "G_1") (pintype "input"))
      (node (ref "IC25") (pin "19") (pinfunction "G_19") (pintype "input"))
      (node (ref "IC29") (pin "6") (pinfunction "O_6") (pintype "output"))
    )
    (net (code "89") (name "Net-(IC27A-G)") (class "Default")
      (node (ref "IC27") (pin "1") (pinfunction "G_1") (pintype "input"))
      (node (ref "IC27") (pin "19") (pinfunction "G_19") (pintype "input"))
      (node (ref "IC29") (pin "10") (pinfunction "O_10") (pintype "output"))
    )
    (net (code "90") (name "PC0") (class "Default")
      (node (ref "IC20") (pin "3") (pinfunction "QA_3") (pintype "output"))
      (node (ref "IC24") (pin "2") (pinfunction "A1_2") (pintype "input"))
      (node (ref "IC25") (pin "2") (pinfunction "A1_2") (pintype "input"))
    )
    (net (code "91") (name "PC1") (class "Default")
      (node (ref "IC20") (pin "2") (pinfunction "QB_2") (pintype "output"))
      (node (ref "IC24") (pin "4") (pinfunction "A2_4") (pintype "input"))
      (node (ref "IC25") (pin "4") (pinfunction "A2_4") (pintype "input"))
    )
    (net (code "92") (name "PC2") (class "Default")
      (node (ref "IC20") (pin "6") (pinfunction "QC_6") (pintype "output"))
      (node (ref "IC24") (pin "6") (pinfunction "A3_6") (pintype "input"))
      (node (ref "IC25") (pin "6") (pinfunction "A3_6") (pintype "input"))
    )
    (net (code "93") (name "PC3") (class "Default")
      (node (ref "IC20") (pin "7") (pinfunction "QD_7") (pintype "output"))
      (node (ref "IC24") (pin "8") (pinfunction "A4_8") (pintype "input"))
      (node (ref "IC25") (pin "8") (pinfunction "A4_8") (pintype "input"))
    )
    (net (code "94") (name "PC4") (class "Default")
      (node (ref "IC21") (pin "3") (pinfunction "QA_3") (pintype "output"))
      (node (ref "IC24") (pin "11") (pinfunction "A1_11") (pintype "input"))
      (node (ref "IC25") (pin "11") (pinfunction "A1_11") (pintype "input"))
    )
    (net (code "95") (name "PC5") (class "Default")
      (node (ref "IC21") (pin "2") (pinfunction "QB_2") (pintype "output"))
      (node (ref "IC24") (pin "13") (pinfunction "A2_13") (pintype "input"))
      (node (ref "IC25") (pin "13") (pinfunction "A2_13") (pintype "input"))
    )
    (net (code "96") (name "PC6") (class "Default")
      (node (ref "IC21") (pin "6") (pinfunction "QC_6") (pintype "output"))
      (node (ref "IC24") (pin "15") (pinfunction "A3_15") (pintype "input"))
      (node (ref "IC25") (pin "15") (pinfunction "A3_15") (pintype "input"))
    )
    (net (code "97") (name "PC7") (class "Default")
      (node (ref "IC21") (pin "7") (pinfunction "QD_7") (pintype "output"))
      (node (ref "IC24") (pin "17") (pinfunction "A4_17") (pintype "input"))
      (node (ref "IC25") (pin "17") (pinfunction "A4_17") (pintype "input"))
    )
    (net (code "98") (name "PCAOUT") (class "Default")
      (node (ref "IC29") (pin "5") (pinfunction "I_5") (pintype "input"))
      (node (ref "IC3") (pin "15") (pinfunction "D3_15") (pintype "tri_state"))
    )
    (net (code "99") (name "PCDOUT") (class "Default")
      (node (ref "IC29") (pin "9") (pinfunction "I_9") (pintype "input"))
      (node (ref "IC3") (pin "13") (pinfunction "D2_13") (pintype "tri_state"))
    )
    (net (code "100") (name "PCINC") (class "Default")
      (node (ref "IC3") (pin "17") (pinfunction "D5_17") (pintype "tri_state"))
    )
    (net (code "101") (name "PCLD") (class "Default")
      (node (ref "IC3") (pin "16") (pinfunction "D4_16") (pintype "tri_state"))
    )
    (net (code "102") (name "R0DATA0") (class "Default")
      (node (ref "IC10") (pin "2") (pinfunction "A1_2") (pintype "input"))
      (node (ref "IC11") (pin "2") (pinfunction "A1_2") (pintype "input"))
      (node (ref "REG-0") (pin "2") (pinfunction "Q1_2") (pintype "output"))
    )
    (net (code "103") (name "R0DATA1") (class "Default")
      (node (ref "IC10") (pin "4") (pinfunction "A2_4") (pintype "input"))
      (node (ref "IC11") (pin "4") (pinfunction "A2_4") (pintype "input"))
      (node (ref "REG-0") (pin "5") (pinfunction "Q2_5") (pintype "output"))
    )
    (net (code "104") (name "R0DATA2") (class "Default")
      (node (ref "IC10") (pin "6") (pinfunction "A3_6") (pintype "input"))
      (node (ref "IC11") (pin "6") (pinfunction "A3_6") (pintype "input"))
      (node (ref "REG-0") (pin "6") (pinfunction "Q3_6") (pintype "output"))
    )
    (net (code "105") (name "R0DATA3") (class "Default")
      (node (ref "IC10") (pin "8") (pinfunction "A4_8") (pintype "input"))
      (node (ref "IC11") (pin "8") (pinfunction "A4_8") (pintype "input"))
      (node (ref "REG-0") (pin "9") (pinfunction "Q4_9") (pintype "output"))
    )
    (net (code "106") (name "R0DATA4") (class "Default")
      (node (ref "IC10") (pin "11") (pinfunction "A1_11") (pintype "input"))
      (node (ref "IC11") (pin "11") (pinfunction "A1_11") (pintype "input"))
      (node (ref "REG-0") (pin "12") (pinfunction "Q5_12") (pintype "output"))
    )
    (net (code "107") (name "R0DATA5") (class "Default")
      (node (ref "IC10") (pin "13") (pinfunction "A2_13") (pintype "input"))
      (node (ref "IC11") (pin "13") (pinfunction "A2_13") (pintype "input"))
      (node (ref "REG-0") (pin "15") (pinfunction "Q6_15") (pintype "output"))
    )
    (net (code "108") (name "R0DATA6") (class "Default")
      (node (ref "IC10") (pin "15") (pinfunction "A3_15") (pintype "input"))
      (node (ref "IC11") (pin "15") (pinfunction "A3_15") (pintype "input"))
      (node (ref "REG-0") (pin "16") (pinfunction "Q7_16") (pintype "output"))
    )
    (net (code "109") (name "R0DATA7") (class "Default")
      (node (ref "IC10") (pin "17") (pinfunction "A4_17") (pintype "input"))
      (node (ref "IC11") (pin "17") (pinfunction "A4_17") (pintype "input"))
      (node (ref "REG-0") (pin "19") (pinfunction "Q8_19") (pintype "output"))
    )
    (net (code "110") (name "R1DATA0") (class "Default")
      (node (ref "IC12") (pin "2") (pinfunction "A1_2") (pintype "input"))
      (node (ref "IC13") (pin "2") (pinfunction "A1_2") (pintype "input"))
      (node (ref "REG-1") (pin "2") (pinfunction "Q1_2") (pintype "output"))
    )
    (net (code "111") (name "R1DATA1") (class "Default")
      (node (ref "IC12") (pin "4") (pinfunction "A2_4") (pintype "input"))
      (node (ref "IC13") (pin "4") (pinfunction "A2_4") (pintype "input"))
      (node (ref "REG-1") (pin "5") (pinfunction "Q2_5") (pintype "output"))
    )
    (net (code "112") (name "R1DATA2") (class "Default")
      (node (ref "IC12") (pin "6") (pinfunction "A3_6") (pintype "input"))
      (node (ref "IC13") (pin "6") (pinfunction "A3_6") (pintype "input"))
      (node (ref "REG-1") (pin "6") (pinfunction "Q3_6") (pintype "output"))
    )
    (net (code "113") (name "R1DATA3") (class "Default")
      (node (ref "IC12") (pin "8") (pinfunction "A4_8") (pintype "input"))
      (node (ref "IC13") (pin "8") (pinfunction "A4_8") (pintype "input"))
      (node (ref "REG-1") (pin "9") (pinfunction "Q4_9") (pintype "output"))
    )
    (net (code "114") (name "R1DATA4") (class "Default")
      (node (ref "IC12") (pin "11") (pinfunction "A1_11") (pintype "input"))
      (node (ref "IC13") (pin "11") (pinfunction "A1_11") (pintype "input"))
      (node (ref "REG-1") (pin "12") (pinfunction "Q5_12") (pintype "output"))
    )
    (net (code "115") (name "R1DATA5") (class "Default")
      (node (ref "IC12") (pin "13") (pinfunction "A2_13") (pintype "input"))
      (node (ref "IC13") (pin "13") (pinfunction "A2_13") (pintype "input"))
      (node (ref "REG-1") (pin "15") (pinfunction "Q6_15") (pintype "output"))
    )
    (net (code "116") (name "R1DATA6") (class "Default")
      (node (ref "IC12") (pin "15") (pinfunction "A3_15") (pintype "input"))
      (node (ref "IC13") (pin "15") (pinfunction "A3_15") (pintype "input"))
      (node (ref "REG-1") (pin "16") (pinfunction "Q7_16") (pintype "output"))
    )
    (net (code "117") (name "R1DATA7") (class "Default")
      (node (ref "IC12") (pin "17") (pinfunction "A4_17") (pintype "input"))
      (node (ref "IC13") (pin "17") (pinfunction "A4_17") (pintype "input"))
      (node (ref "REG-1") (pin "19") (pinfunction "Q8_19") (pintype "output"))
    )
    (net (code "118") (name "R2DATA0") (class "Default")
      (node (ref "IC14") (pin "2") (pinfunction "A1_2") (pintype "input"))
      (node (ref "IC16") (pin "2") (pinfunction "A1_2") (pintype "input"))
      (node (ref "REG-2") (pin "2") (pinfunction "Q1_2") (pintype "output"))
    )
    (net (code "119") (name "R2DATA1") (class "Default")
      (node (ref "IC14") (pin "4") (pinfunction "A2_4") (pintype "input"))
      (node (ref "IC16") (pin "4") (pinfunction "A2_4") (pintype "input"))
      (node (ref "REG-2") (pin "5") (pinfunction "Q2_5") (pintype "output"))
    )
    (net (code "120") (name "R2DATA2") (class "Default")
      (node (ref "IC14") (pin "6") (pinfunction "A3_6") (pintype "input"))
      (node (ref "IC16") (pin "6") (pinfunction "A3_6") (pintype "input"))
      (node (ref "REG-2") (pin "6") (pinfunction "Q3_6") (pintype "output"))
    )
    (net (code "121") (name "R2DATA3") (class "Default")
      (node (ref "IC14") (pin "8") (pinfunction "A4_8") (pintype "input"))
      (node (ref "IC16") (pin "8") (pinfunction "A4_8") (pintype "input"))
      (node (ref "REG-2") (pin "9") (pinfunction "Q4_9") (pintype "output"))
    )
    (net (code "122") (name "R2DATA4") (class "Default")
      (node (ref "IC14") (pin "11") (pinfunction "A1_11") (pintype "input"))
      (node (ref "IC16") (pin "11") (pinfunction "A1_11") (pintype "input"))
      (node (ref "REG-2") (pin "12") (pinfunction "Q5_12") (pintype "output"))
    )
    (net (code "123") (name "R2DATA5") (class "Default")
      (node (ref "IC14") (pin "13") (pinfunction "A2_13") (pintype "input"))
      (node (ref "IC16") (pin "13") (pinfunction "A2_13") (pintype "input"))
      (node (ref "REG-2") (pin "15") (pinfunction "Q6_15") (pintype "output"))
    )
    (net (code "124") (name "R2DATA6") (class "Default")
      (node (ref "IC14") (pin "15") (pinfunction "A3_15") (pintype "input"))
      (node (ref "IC16") (pin "15") (pinfunction "A3_15") (pintype "input"))
      (node (ref "REG-2") (pin "16") (pinfunction "Q7_16") (pintype "output"))
    )
    (net (code "125") (name "R2DATA7") (class "Default")
      (node (ref "IC14") (pin "17") (pinfunction "A4_17") (pintype "input"))
      (node (ref "IC16") (pin "17") (pinfunction "A4_17") (pintype "input"))
      (node (ref "REG-2") (pin "19") (pinfunction "Q8_19") (pintype "output"))
    )
    (net (code "126") (name "R3DATA0") (class "Default")
      (node (ref "IC15") (pin "2") (pinfunction "A1_2") (pintype "input"))
      (node (ref "IC17") (pin "2") (pinfunction "A1_2") (pintype "input"))
      (node (ref "REG-3") (pin "2") (pinfunction "Q1_2") (pintype "output"))
    )
    (net (code "127") (name "R3DATA1") (class "Default")
      (node (ref "IC15") (pin "4") (pinfunction "A2_4") (pintype "input"))
      (node (ref "IC17") (pin "4") (pinfunction "A2_4") (pintype "input"))
      (node (ref "REG-3") (pin "5") (pinfunction "Q2_5") (pintype "output"))
    )
    (net (code "128") (name "R3DATA2") (class "Default")
      (node (ref "IC15") (pin "6") (pinfunction "A3_6") (pintype "input"))
      (node (ref "IC17") (pin "6") (pinfunction "A3_6") (pintype "input"))
      (node (ref "REG-3") (pin "6") (pinfunction "Q3_6") (pintype "output"))
    )
    (net (code "129") (name "R3DATA3") (class "Default")
      (node (ref "IC15") (pin "8") (pinfunction "A4_8") (pintype "input"))
      (node (ref "IC17") (pin "8") (pinfunction "A4_8") (pintype "input"))
      (node (ref "REG-3") (pin "9") (pinfunction "Q4_9") (pintype "output"))
    )
    (net (code "130") (name "R3DATA4") (class "Default")
      (node (ref "IC15") (pin "11") (pinfunction "A1_11") (pintype "input"))
      (node (ref "IC17") (pin "11") (pinfunction "A1_11") (pintype "input"))
      (node (ref "REG-3") (pin "12") (pinfunction "Q5_12") (pintype "output"))
    )
    (net (code "131") (name "R3DATA5") (class "Default")
      (node (ref "IC15") (pin "13") (pinfunction "A2_13") (pintype "input"))
      (node (ref "IC17") (pin "13") (pinfunction "A2_13") (pintype "input"))
      (node (ref "REG-3") (pin "15") (pinfunction "Q6_15") (pintype "output"))
    )
    (net (code "132") (name "R3DATA6") (class "Default")
      (node (ref "IC15") (pin "15") (pinfunction "A3_15") (pintype "input"))
      (node (ref "IC17") (pin "15") (pinfunction "A3_15") (pintype "input"))
      (node (ref "REG-3") (pin "16") (pinfunction "Q7_16") (pintype "output"))
    )
    (net (code "133") (name "R3DATA7") (class "Default")
      (node (ref "IC15") (pin "17") (pinfunction "A4_17") (pintype "input"))
      (node (ref "IC17") (pin "17") (pinfunction "A4_17") (pintype "input"))
      (node (ref "REG-3") (pin "19") (pinfunction "Q8_19") (pintype "output"))
    )
    (net (code "134") (name "RAOUT0") (class "Default")
      (node (ref "IC18") (pin "1") (pinfunction "I_1") (pintype "input"))
      (node (ref "IC2") (pin "11") (pinfunction "D0_11") (pintype "tri_state"))
    )
    (net (code "135") (name "RAOUT1") (class "Default")
      (node (ref "IC18") (pin "3") (pinfunction "I_3") (pintype "input"))
      (node (ref "IC2") (pin "12") (pinfunction "D1_12") (pintype "tri_state"))
    )
    (net (code "136") (name "RAOUT2") (class "Default")
      (node (ref "IC18") (pin "5") (pinfunction "I_5") (pintype "input"))
      (node (ref "IC2") (pin "13") (pinfunction "D2_13") (pintype "tri_state"))
    )
    (net (code "137") (name "RAOUT3") (class "Default")
      (node (ref "IC18") (pin "9") (pinfunction "I_9") (pintype "input"))
      (node (ref "IC2") (pin "15") (pinfunction "D3_15") (pintype "tri_state"))
    )
    (net (code "138") (name "RCT") (class "Default")
      (node (ref "IC4") (pin "11") (pinfunction "D0_11") (pintype "tri_state"))
    )
    (net (code "139") (name "RDIN0") (class "Default")
      (node (ref "IC1") (pin "16") (pinfunction "D4_16") (pintype "tri_state"))
      (node (ref "REG-0") (pin "11") (pinfunction "CLK_11") (pintype "input"))
    )
    (net (code "140") (name "RDIN1") (class "Default")
      (node (ref "IC1") (pin "17") (pinfunction "D5_17") (pintype "tri_state"))
      (node (ref "REG-1") (pin "11") (pinfunction "CLK_11") (pintype "input"))
    )
    (net (code "141") (name "RDIN2") (class "Default")
      (node (ref "IC1") (pin "18") (pinfunction "D6_18") (pintype "tri_state"))
      (node (ref "REG-2") (pin "11") (pinfunction "CLK_11") (pintype "input"))
    )
    (net (code "142") (name "RDIN3") (class "Default")
      (node (ref "IC1") (pin "19") (pinfunction "D7_19") (pintype "tri_state"))
      (node (ref "REG-3") (pin "11") (pinfunction "CLK_11") (pintype "input"))
    )
    (net (code "143") (name "RDOUT0") (class "Default")
      (node (ref "IC1") (pin "11") (pinfunction "D0_11") (pintype "tri_state"))
      (node (ref "IC19") (pin "3") (pinfunction "I_3") (pintype "input"))
    )
    (net (code "144") (name "RDOUT1") (class "Default")
      (node (ref "IC1") (pin "12") (pinfunction "D1_12") (pintype "tri_state"))
      (node (ref "IC19") (pin "1") (pinfunction "I_1") (pintype "input"))
    )
    (net (code "145") (name "RDOUT2") (class "Default")
      (node (ref "IC1") (pin "13") (pinfunction "D2_13") (pintype "tri_state"))
      (node (ref "IC18") (pin "13") (pinfunction "I_13") (pintype "input"))
    )
    (net (code "146") (name "RDOUT3") (class "Default")
      (node (ref "IC1") (pin "15") (pinfunction "D3_15") (pintype "tri_state"))
      (node (ref "IC18") (pin "11") (pinfunction "I_11") (pintype "input"))
    )
    (net (code "147") (name "RESET") (class "Default")
      (node (ref "IC8") (pin "1") (pinfunction "I0_1") (pintype "input"))
      (node (ref "IC9") (pin "3") (pinfunction "I_3") (pintype "input"))
    )
    (net (code "148") (name "RLD") (class "Default")
      (node (ref "IC3") (pin "19") (pinfunction "D7_19") (pintype "tri_state"))
    )
    (net (code "149") (name "RSTUC") (class "Default")
      (node (ref "IC4") (pin "19") (pinfunction "D7_19") (pintype "tri_state"))
      (node (ref "IC8") (pin "2") (pinfunction "I1_2") (pintype "input"))
    )
    (net (code "150") (name "S0") (class "Default")
      (node (ref "IC1") (pin "10") (pinfunction "A0_10") (pintype "input"))
      (node (ref "IC2") (pin "10") (pinfunction "A0_10") (pintype "input"))
      (node (ref "IC3") (pin "10") (pinfunction "A0_10") (pintype "input"))
      (node (ref "IC30") (pin "10") (pinfunction "A0_10") (pintype "input"))
      (node (ref "IC4") (pin "10") (pinfunction "A0_10") (pintype "input"))
      (node (ref "IC5") (pin "10") (pinfunction "A0_10") (pintype "input"))
      (node (ref "UCPC-") (pin "3") (pinfunction "QA_3") (pintype "output"))
    )
    (net (code "151") (name "S1") (class "Default")
      (node (ref "IC1") (pin "9") (pinfunction "A1_9") (pintype "input"))
      (node (ref "IC2") (pin "9") (pinfunction "A1_9") (pintype "input"))
      (node (ref "IC3") (pin "9") (pinfunction "A1_9") (pintype "input"))
      (node (ref "IC30") (pin "9") (pinfunction "A1_9") (pintype "input"))
      (node (ref "IC4") (pin "9") (pinfunction "A1_9") (pintype "input"))
      (node (ref "IC5") (pin "9") (pinfunction "A1_9") (pintype "input"))
      (node (ref "UCPC-") (pin "4") (pinfunction "QB_4") (pintype "output"))
    )
    (net (code "152") (name "S2") (class "Default")
      (node (ref "IC1") (pin "8") (pinfunction "A2_8") (pintype "input"))
      (node (ref "IC2") (pin "8") (pinfunction "A2_8") (pintype "input"))
      (node (ref "IC3") (pin "8") (pinfunction "A2_8") (pintype "input"))
      (node (ref "IC30") (pin "8") (pinfunction "A2_8") (pintype "input"))
      (node (ref "IC4") (pin "8") (pinfunction "A2_8") (pintype "input"))
      (node (ref "IC5") (pin "8") (pinfunction "A2_8") (pintype "input"))
      (node (ref "UCPC-") (pin "5") (pinfunction "QC_5") (pintype "output"))
    )
    (net (code "153") (name "S3") (class "Default")
      (node (ref "IC1") (pin "7") (pinfunction "A3_7") (pintype "input"))
      (node (ref "IC2") (pin "7") (pinfunction "A3_7") (pintype "input"))
      (node (ref "IC3") (pin "7") (pinfunction "A3_7") (pintype "input"))
      (node (ref "IC30") (pin "7") (pinfunction "A3_7") (pintype "input"))
      (node (ref "IC4") (pin "7") (pinfunction "A3_7") (pintype "input"))
      (node (ref "IC5") (pin "7") (pinfunction "A3_7") (pintype "input"))
      (node (ref "UCPC-") (pin "13") (pinfunction "A_13") (pintype "input"))
      (node (ref "UCPC-") (pin "6") (pinfunction "QD_6") (pintype "output"))
    )
    (net (code "154") (name "S4") (class "Default")
      (node (ref "IC1") (pin "6") (pinfunction "A4_6") (pintype "input"))
      (node (ref "IC2") (pin "6") (pinfunction "A4_6") (pintype "input"))
      (node (ref "IC3") (pin "6") (pinfunction "A4_6") (pintype "input"))
      (node (ref "IC30") (pin "6") (pinfunction "A4_6") (pintype "input"))
      (node (ref "IC4") (pin "6") (pinfunction "A4_6") (pintype "input"))
      (node (ref "IC5") (pin "6") (pinfunction "A4_6") (pintype "input"))
      (node (ref "UCPC-") (pin "11") (pinfunction "QA_11") (pintype "output"))
    )
    (net (code "155") (name "S5") (class "Default")
      (node (ref "IC1") (pin "5") (pinfunction "A5_5") (pintype "input"))
      (node (ref "IC2") (pin "5") (pinfunction "A5_5") (pintype "input"))
      (node (ref "IC3") (pin "5") (pinfunction "A5_5") (pintype "input"))
      (node (ref "IC30") (pin "5") (pinfunction "A5_5") (pintype "input"))
      (node (ref "IC4") (pin "5") (pinfunction "A5_5") (pintype "input"))
      (node (ref "IC5") (pin "5") (pinfunction "A5_5") (pintype "input"))
      (node (ref "INS-REG") (pin "2") (pinfunction "Q1_2") (pintype "output"))
    )
    (net (code "156") (name "S6") (class "Default")
      (node (ref "IC1") (pin "4") (pinfunction "A6_4") (pintype "input"))
      (node (ref "IC2") (pin "4") (pinfunction "A6_4") (pintype "input"))
      (node (ref "IC3") (pin "4") (pinfunction "A6_4") (pintype "input"))
      (node (ref "IC30") (pin "4") (pinfunction "A6_4") (pintype "input"))
      (node (ref "IC4") (pin "4") (pinfunction "A6_4") (pintype "input"))
      (node (ref "IC5") (pin "4") (pinfunction "A6_4") (pintype "input"))
      (node (ref "INS-REG") (pin "5") (pinfunction "Q2_5") (pintype "output"))
    )
    (net (code "157") (name "S7") (class "Default")
      (node (ref "IC1") (pin "3") (pinfunction "A7_3") (pintype "input"))
      (node (ref "IC2") (pin "3") (pinfunction "A7_3") (pintype "input"))
      (node (ref "IC3") (pin "3") (pinfunction "A7_3") (pintype "input"))
      (node (ref "IC30") (pin "3") (pinfunction "A7_3") (pintype "input"))
      (node (ref "IC4") (pin "3") (pinfunction "A7_3") (pintype "input"))
      (node (ref "IC5") (pin "3") (pinfunction "A7_3") (pintype "input"))
      (node (ref "INS-REG") (pin "6") (pinfunction "Q3_6") (pintype "output"))
    )
    (net (code "158") (name "S8") (class "Default")
      (node (ref "IC1") (pin "25") (pinfunction "A8_25") (pintype "input"))
      (node (ref "IC2") (pin "25") (pinfunction "A8_25") (pintype "input"))
      (node (ref "IC3") (pin "25") (pinfunction "A8_25") (pintype "input"))
      (node (ref "IC30") (pin "25") (pinfunction "A8_25") (pintype "input"))
      (node (ref "IC4") (pin "25") (pinfunction "A8_25") (pintype "input"))
      (node (ref "IC5") (pin "25") (pinfunction "A8_25") (pintype "input"))
      (node (ref "INS-REG") (pin "9") (pinfunction "Q4_9") (pintype "output"))
    )
    (net (code "159") (name "S9") (class "Default")
      (node (ref "IC1") (pin "24") (pinfunction "A9_24") (pintype "input"))
      (node (ref "IC2") (pin "24") (pinfunction "A9_24") (pintype "input"))
      (node (ref "IC3") (pin "24") (pinfunction "A9_24") (pintype "input"))
      (node (ref "IC30") (pin "24") (pinfunction "A9_24") (pintype "input"))
      (node (ref "IC4") (pin "24") (pinfunction "A9_24") (pintype "input"))
      (node (ref "IC5") (pin "24") (pinfunction "A9_24") (pintype "input"))
      (node (ref "INS-REG") (pin "12") (pinfunction "Q5_12") (pintype "output"))
    )
    (net (code "160") (name "S10") (class "Default")
      (node (ref "IC1") (pin "21") (pinfunction "A10_21") (pintype "input"))
      (node (ref "IC2") (pin "21") (pinfunction "A10_21") (pintype "input"))
      (node (ref "IC3") (pin "21") (pinfunction "A10_21") (pintype "input"))
      (node (ref "IC30") (pin "21") (pinfunction "A10_21") (pintype "input"))
      (node (ref "IC4") (pin "21") (pinfunction "A10_21") (pintype "input"))
      (node (ref "IC5") (pin "21") (pinfunction "A10_21") (pintype "input"))
      (node (ref "INS-REG") (pin "15") (pinfunction "Q6_15") (pintype "output"))
    )
    (net (code "161") (name "S11") (class "Default")
      (node (ref "IC1") (pin "23") (pinfunction "A11_23") (pintype "input"))
      (node (ref "IC2") (pin "23") (pinfunction "A11_23") (pintype "input"))
      (node (ref "IC3") (pin "23") (pinfunction "A11_23") (pintype "input"))
      (node (ref "IC30") (pin "23") (pinfunction "A11_23") (pintype "input"))
      (node (ref "IC4") (pin "23") (pinfunction "A11_23") (pintype "input"))
      (node (ref "IC5") (pin "23") (pinfunction "A11_23") (pintype "input"))
      (node (ref "INS-REG") (pin "16") (pinfunction "Q7_16") (pintype "output"))
    )
    (net (code "162") (name "S12") (class "Default")
      (node (ref "IC1") (pin "2") (pinfunction "A12_2") (pintype "input"))
      (node (ref "IC2") (pin "2") (pinfunction "A12_2") (pintype "input"))
      (node (ref "IC3") (pin "2") (pinfunction "A12_2") (pintype "input"))
      (node (ref "IC30") (pin "2") (pinfunction "A12_2") (pintype "input"))
      (node (ref "IC4") (pin "2") (pinfunction "A12_2") (pintype "input"))
      (node (ref "IC5") (pin "2") (pinfunction "A12_2") (pintype "input"))
      (node (ref "INS-REG") (pin "19") (pinfunction "Q8_19") (pintype "output"))
    )
    (net (code "163") (name "SPAOUT") (class "Default")
      (node (ref "IC29") (pin "11") (pinfunction "I_11") (pintype "input"))
      (node (ref "IC4") (pin "17") (pinfunction "D5_17") (pintype "tri_state"))
    )
    (net (code "164") (name "SPDIN") (class "Default")
      (node (ref "IC4") (pin "16") (pinfunction "D4_16") (pintype "tri_state"))
    )
    (net (code "165") (name "VCC") (class "Default")
      (node (ref "IC1") (pin "28") (pinfunction "VCC_28") (pintype "power_in"))
      (node (ref "IC2") (pin "1") (pinfunction "VPP_1") (pintype "input"))
      (node (ref "IC2") (pin "27") (pinfunction "PGM_27") (pintype "input"))
      (node (ref "IC2") (pin "28") (pinfunction "VCC_28") (pintype "power_in"))
      (node (ref "IC3") (pin "1") (pinfunction "VPP_1") (pintype "input"))
      (node (ref "IC3") (pin "27") (pinfunction "PGM_27") (pintype "input"))
      (node (ref "IC3") (pin "28") (pinfunction "VCC_28") (pintype "power_in"))
      (node (ref "IC30") (pin "1") (pinfunction "VPP_1") (pintype "input"))
      (node (ref "IC30") (pin "27") (pinfunction "PGM_27") (pintype "input"))
      (node (ref "IC30") (pin "28") (pinfunction "VCC_28") (pintype "power_in"))
      (node (ref "IC4") (pin "1") (pinfunction "VPP_1") (pintype "input"))
      (node (ref "IC4") (pin "27") (pinfunction "PGM_27") (pintype "input"))
      (node (ref "IC4") (pin "28") (pinfunction "VCC_28") (pintype "power_in"))
      (node (ref "IC5") (pin "1") (pinfunction "VPP_1") (pintype "input"))
      (node (ref "IC5") (pin "27") (pinfunction "PGM_27") (pintype "input"))
      (node (ref "IC5") (pin "28") (pinfunction "VCC_28") (pintype "power_in"))
    )
    (net (code "166") (name "unconnected-(IC1-NC-Pad26)") (class "Default")
      (node (ref "IC1") (pin "26") (pinfunction "NC_26") (pintype "no_connect"))
    )
    (net (code "167") (name "unconnected-(IC1-PGM-Pad27)") (class "Default")
      (node (ref "IC1") (pin "27") (pinfunction "PGM_27") (pintype "input"))
    )
    (net (code "168") (name "unconnected-(IC1-VPP-Pad1)") (class "Default")
      (node (ref "IC1") (pin "1") (pinfunction "VPP_1") (pintype "input"))
    )
    (net (code "169") (name "unconnected-(IC2-NC-Pad26)") (class "Default")
      (node (ref "IC2") (pin "26") (pinfunction "NC_26") (pintype "no_connect"))
    )
    (net (code "170") (name "unconnected-(IC3-NC-Pad26)") (class "Default")
      (node (ref "IC3") (pin "26") (pinfunction "NC_26") (pintype "no_connect"))
    )
    (net (code "171") (name "unconnected-(IC4-NC-Pad26)") (class "Default")
      (node (ref "IC4") (pin "26") (pinfunction "NC_26") (pintype "no_connect"))
    )
    (net (code "172") (name "unconnected-(IC5-NC-Pad26)") (class "Default")
      (node (ref "IC5") (pin "26") (pinfunction "NC_26") (pintype "no_connect"))
    )
    (net (code "173") (name "unconnected-(IC20A-CLK-Pad14)") (class "Default")
      (node (ref "IC20") (pin "14") (pinfunction "CLK_14") (pintype "input"))
    )
    (net (code "174") (name "unconnected-(IC20A-CTE-Pad4)") (class "Default")
      (node (ref "IC20") (pin "4") (pinfunction "CTE_4") (pintype "input"))
    )
    (net (code "175") (name "unconnected-(IC20A-D{slash}~{U}-Pad5)") (class "Default")
      (node (ref "IC20") (pin "5") (pinfunction "D/~{U}_5") (pintype "input"))
    )
    (net (code "176") (name "unconnected-(IC20A-LD-Pad11)") (class "Default")
      (node (ref "IC20") (pin "11") (pinfunction "LD_11") (pintype "input"))
    )
    (net (code "177") (name "unconnected-(IC20A-MX{slash}MN-Pad12)") (class "Default")
      (node (ref "IC20") (pin "12") (pinfunction "MX/MN_12") (pintype "output"))
    )
    (net (code "178") (name "unconnected-(IC20A-RCO-Pad13)") (class "Default")
      (node (ref "IC20") (pin "13") (pinfunction "RCO_13") (pintype "output"))
    )
    (net (code "179") (name "unconnected-(IC21A-CLK-Pad14)") (class "Default")
      (node (ref "IC21") (pin "14") (pinfunction "CLK_14") (pintype "input"))
    )
    (net (code "180") (name "unconnected-(IC21A-CTE-Pad4)") (class "Default")
      (node (ref "IC21") (pin "4") (pinfunction "CTE_4") (pintype "input"))
    )
    (net (code "181") (name "unconnected-(IC21A-D{slash}~{U}-Pad5)") (class "Default")
      (node (ref "IC21") (pin "5") (pinfunction "D/~{U}_5") (pintype "input"))
    )
    (net (code "182") (name "unconnected-(IC21A-LD-Pad11)") (class "Default")
      (node (ref "IC21") (pin "11") (pinfunction "LD_11") (pintype "input"))
    )
    (net (code "183") (name "unconnected-(IC21A-MX{slash}MN-Pad12)") (class "Default")
      (node (ref "IC21") (pin "12") (pinfunction "MX/MN_12") (pintype "output"))
    )
    (net (code "184") (name "unconnected-(IC21A-RCO-Pad13)") (class "Default")
      (node (ref "IC21") (pin "13") (pinfunction "RCO_13") (pintype "output"))
    )
    (net (code "185") (name "unconnected-(IC22A-CLK-Pad14)") (class "Default")
      (node (ref "IC22") (pin "14") (pinfunction "CLK_14") (pintype "input"))
    )
    (net (code "186") (name "unconnected-(IC22A-CTE-Pad4)") (class "Default")
      (node (ref "IC22") (pin "4") (pinfunction "CTE_4") (pintype "input"))
    )
    (net (code "187") (name "unconnected-(IC22A-D{slash}~{U}-Pad5)") (class "Default")
      (node (ref "IC22") (pin "5") (pinfunction "D/~{U}_5") (pintype "input"))
    )
    (net (code "188") (name "unconnected-(IC22A-LD-Pad11)") (class "Default")
      (node (ref "IC22") (pin "11") (pinfunction "LD_11") (pintype "input"))
    )
    (net (code "189") (name "unconnected-(IC22A-MX{slash}MN-Pad12)") (class "Default")
      (node (ref "IC22") (pin "12") (pinfunction "MX/MN_12") (pintype "output"))
    )
    (net (code "190") (name "unconnected-(IC22A-RCO-Pad13)") (class "Default")
      (node (ref "IC22") (pin "13") (pinfunction "RCO_13") (pintype "output"))
    )
    (net (code "191") (name "unconnected-(IC23A-CLK-Pad14)") (class "Default")
      (node (ref "IC23") (pin "14") (pinfunction "CLK_14") (pintype "input"))
    )
    (net (code "192") (name "unconnected-(IC23A-CTE-Pad4)") (class "Default")
      (node (ref "IC23") (pin "4") (pinfunction "CTE_4") (pintype "input"))
    )
    (net (code "193") (name "unconnected-(IC23A-D{slash}~{U}-Pad5)") (class "Default")
      (node (ref "IC23") (pin "5") (pinfunction "D/~{U}_5") (pintype "input"))
    )
    (net (code "194") (name "unconnected-(IC23A-LD-Pad11)") (class "Default")
      (node (ref "IC23") (pin "11") (pinfunction "LD_11") (pintype "input"))
    )
    (net (code "195") (name "unconnected-(IC23A-MX{slash}MN-Pad12)") (class "Default")
      (node (ref "IC23") (pin "12") (pinfunction "MX/MN_12") (pintype "output"))
    )
    (net (code "196") (name "unconnected-(IC23A-RCO-Pad13)") (class "Default")
      (node (ref "IC23") (pin "13") (pinfunction "RCO_13") (pintype "output"))
    )
    (net (code "197") (name "unconnected-(IC26A-CLK-Pad11)") (class "Default")
      (node (ref "IC26") (pin "11") (pinfunction "CLK_11") (pintype "input"))
    )
    (net (code "198") (name "unconnected-(IC26A-CLR-Pad1)") (class "Default")
      (node (ref "IC26") (pin "1") (pinfunction "CLR_1") (pintype "input"))
    )
    (net (code "199") (name "unconnected-(IC27A-Y1-Pad18)") (class "Default")
      (node (ref "IC27") (pin "18") (pinfunction "Y1_18") (pintype "tri_state"))
    )
    (net (code "200") (name "unconnected-(IC27A-Y4-Pad12)") (class "Default")
      (node (ref "IC27") (pin "12") (pinfunction "Y4_12") (pintype "tri_state"))
    )
    (net (code "201") (name "unconnected-(IC27B-Y1-Pad9)") (class "Default")
      (node (ref "IC27") (pin "9") (pinfunction "Y1_9") (pintype "tri_state"))
    )
    (net (code "202") (name "unconnected-(IC27B-Y2-Pad7)") (class "Default")
      (node (ref "IC27") (pin "7") (pinfunction "Y2_7") (pintype "tri_state"))
    )
    (net (code "203") (name "unconnected-(IC27B-Y3-Pad5)") (class "Default")
      (node (ref "IC27") (pin "5") (pinfunction "Y3_5") (pintype "tri_state"))
    )
    (net (code "204") (name "unconnected-(IC27B-Y4-Pad3)") (class "Default")
      (node (ref "IC27") (pin "3") (pinfunction "Y4_3") (pintype "tri_state"))
    )
    (net (code "205") (name "unconnected-(IC30-D5-Pad17)") (class "Default")
      (node (ref "IC30") (pin "17") (pinfunction "D5_17") (pintype "tri_state"))
    )
    (net (code "206") (name "unconnected-(IC30-D6-Pad18)") (class "Default")
      (node (ref "IC30") (pin "18") (pinfunction "D6_18") (pintype "tri_state"))
    )
    (net (code "207") (name "unconnected-(IC30-D7-Pad19)") (class "Default")
      (node (ref "IC30") (pin "19") (pinfunction "D7_19") (pintype "tri_state"))
    )
    (net (code "208") (name "unconnected-(IC30-NC-Pad26)") (class "Default")
      (node (ref "IC30") (pin "26") (pinfunction "NC_26") (pintype "no_connect"))
    )
    (net (code "209") (name "unconnected-(INS-REGA-CLK-Pad11)") (class "Default")
      (node (ref "INS-REG") (pin "11") (pinfunction "CLK_11") (pintype "input"))
    )
    (net (code "210") (name "unconnected-(INS-REGA-CLR-Pad1)") (class "Default")
      (node (ref "INS-REG") (pin "1") (pinfunction "CLR_1") (pintype "input"))
    )
    (net (code "211") (name "unconnected-(UCPC-A-A-Pad1)") (class "Default")
      (node (ref "UCPC-") (pin "1") (pinfunction "A_1") (pintype "input"))
    )
    (net (code "212") (name "unconnected-(UCPC-B-QB-Pad10)") (class "Default")
      (node (ref "UCPC-") (pin "10") (pinfunction "QB_10") (pintype "output"))
    )
    (net (code "213") (name "unconnected-(UCPC-B-QC-Pad9)") (class "Default")
      (node (ref "UCPC-") (pin "9") (pinfunction "QC_9") (pintype "output"))
    )
    (net (code "214") (name "unconnected-(UCPC-B-QD-Pad8)") (class "Default")
      (node (ref "UCPC-") (pin "8") (pinfunction "QD_8") (pintype "output"))
    )
  )
)
